# STM32F407VET6_4Layer_Sheet.net
KiCad netlist of a schematic drawn in Altium Designer
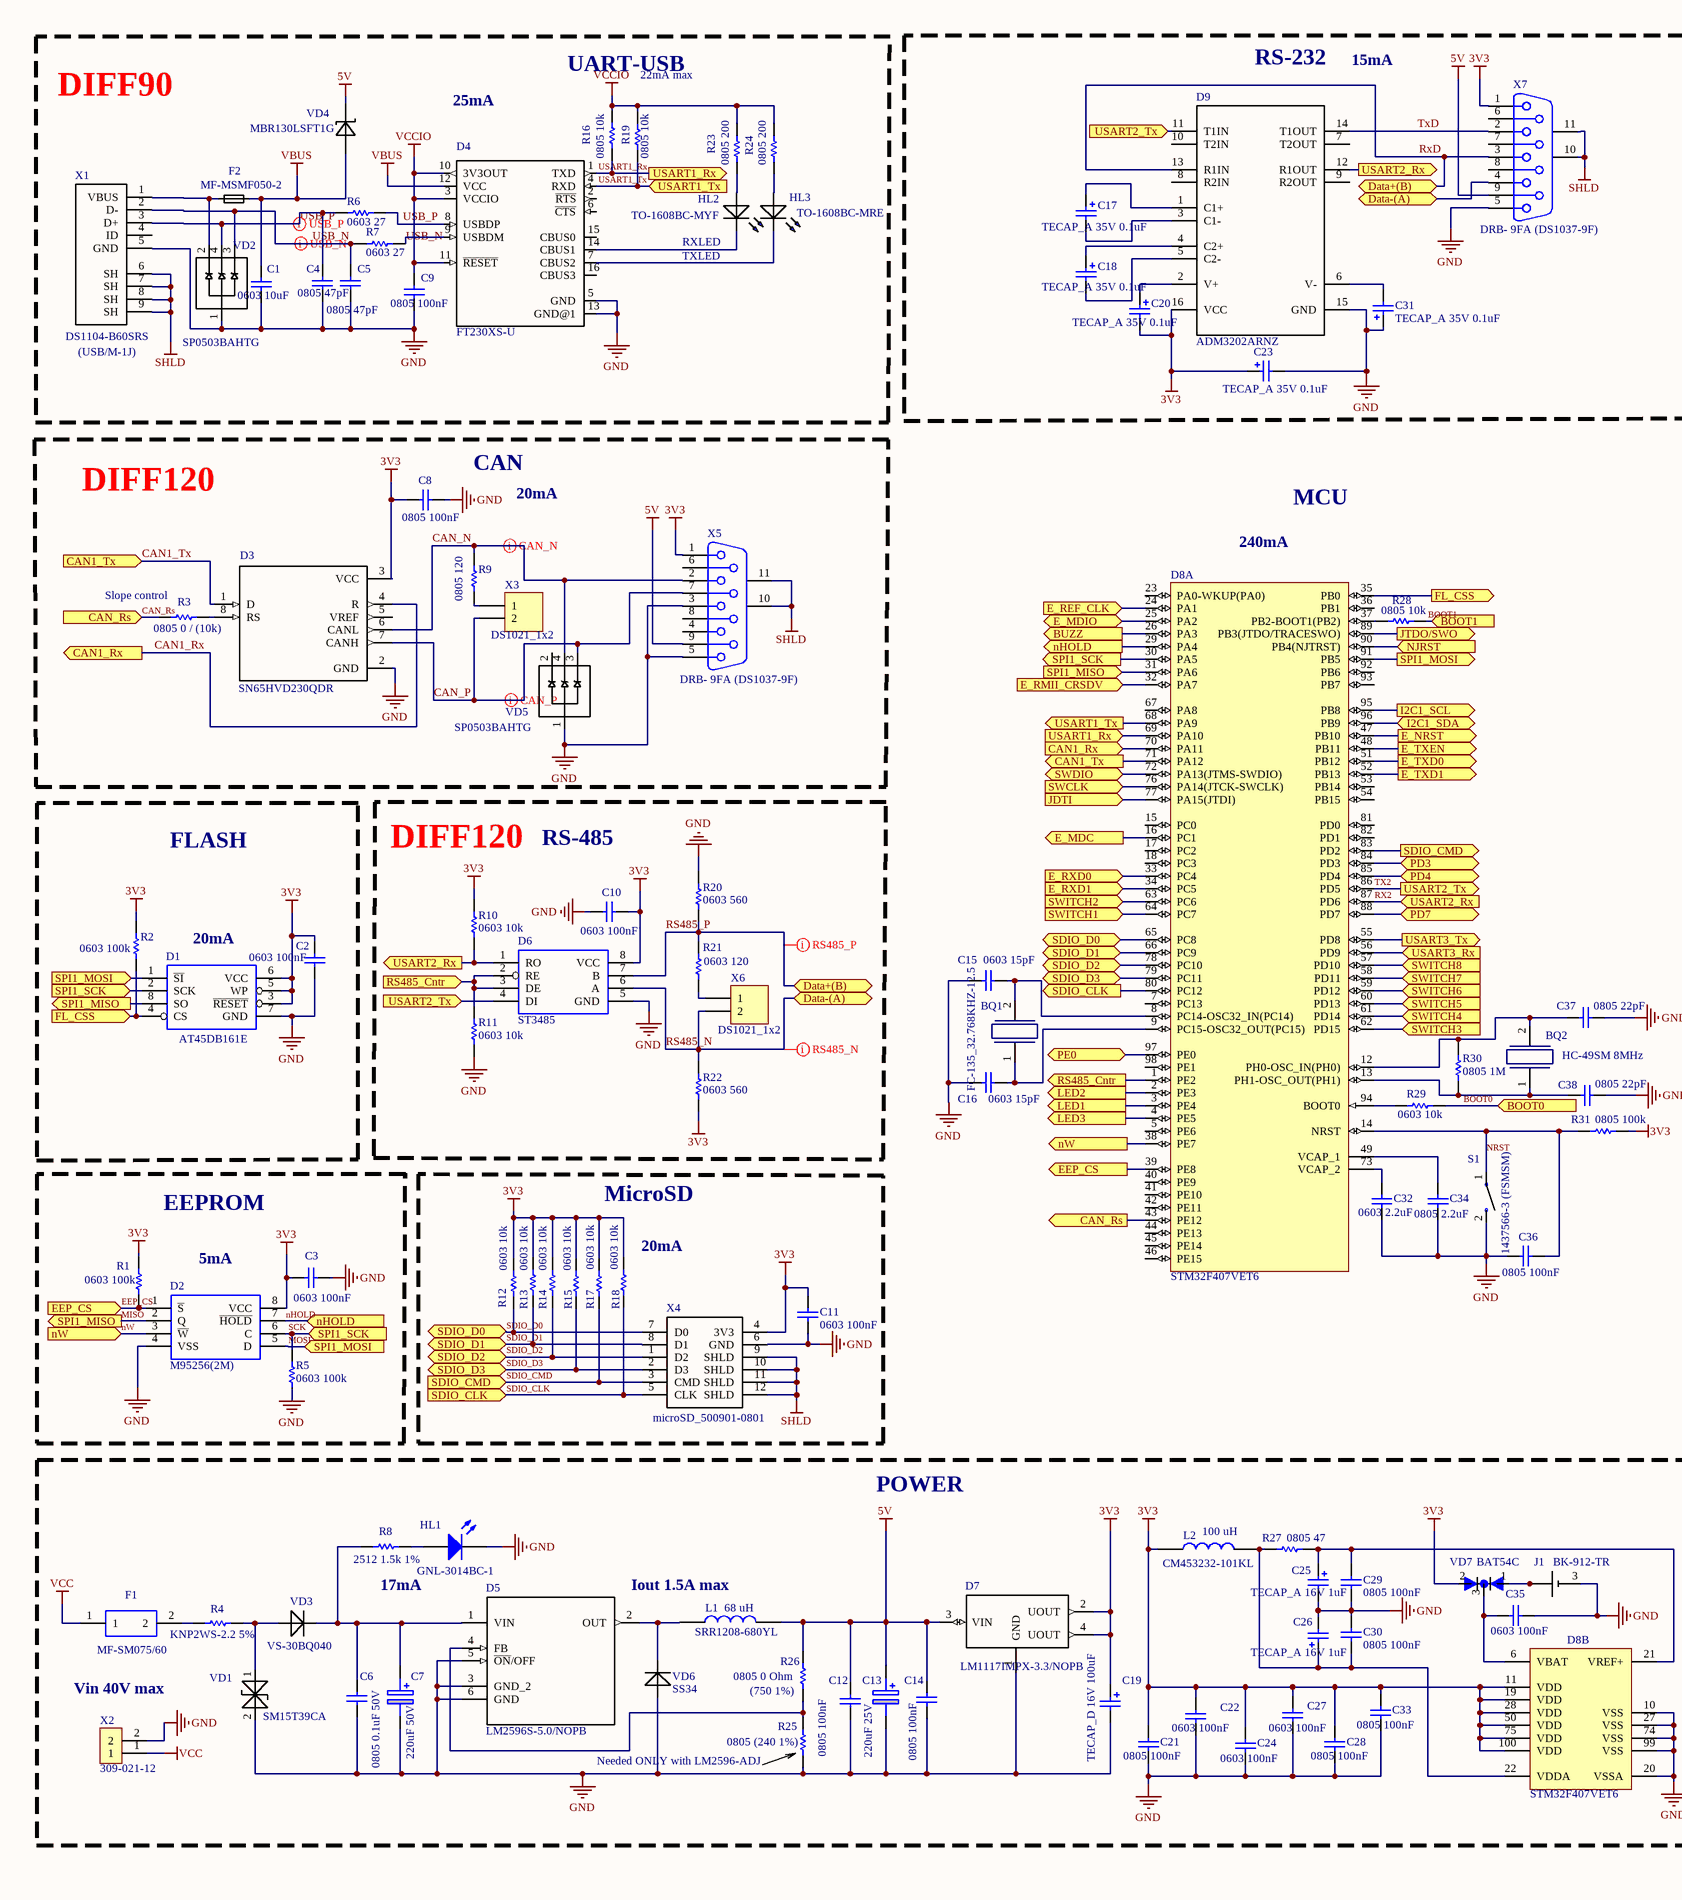
[diagram p0: STM32F407VET6_4Layer_Sheet.SchDoc, left]
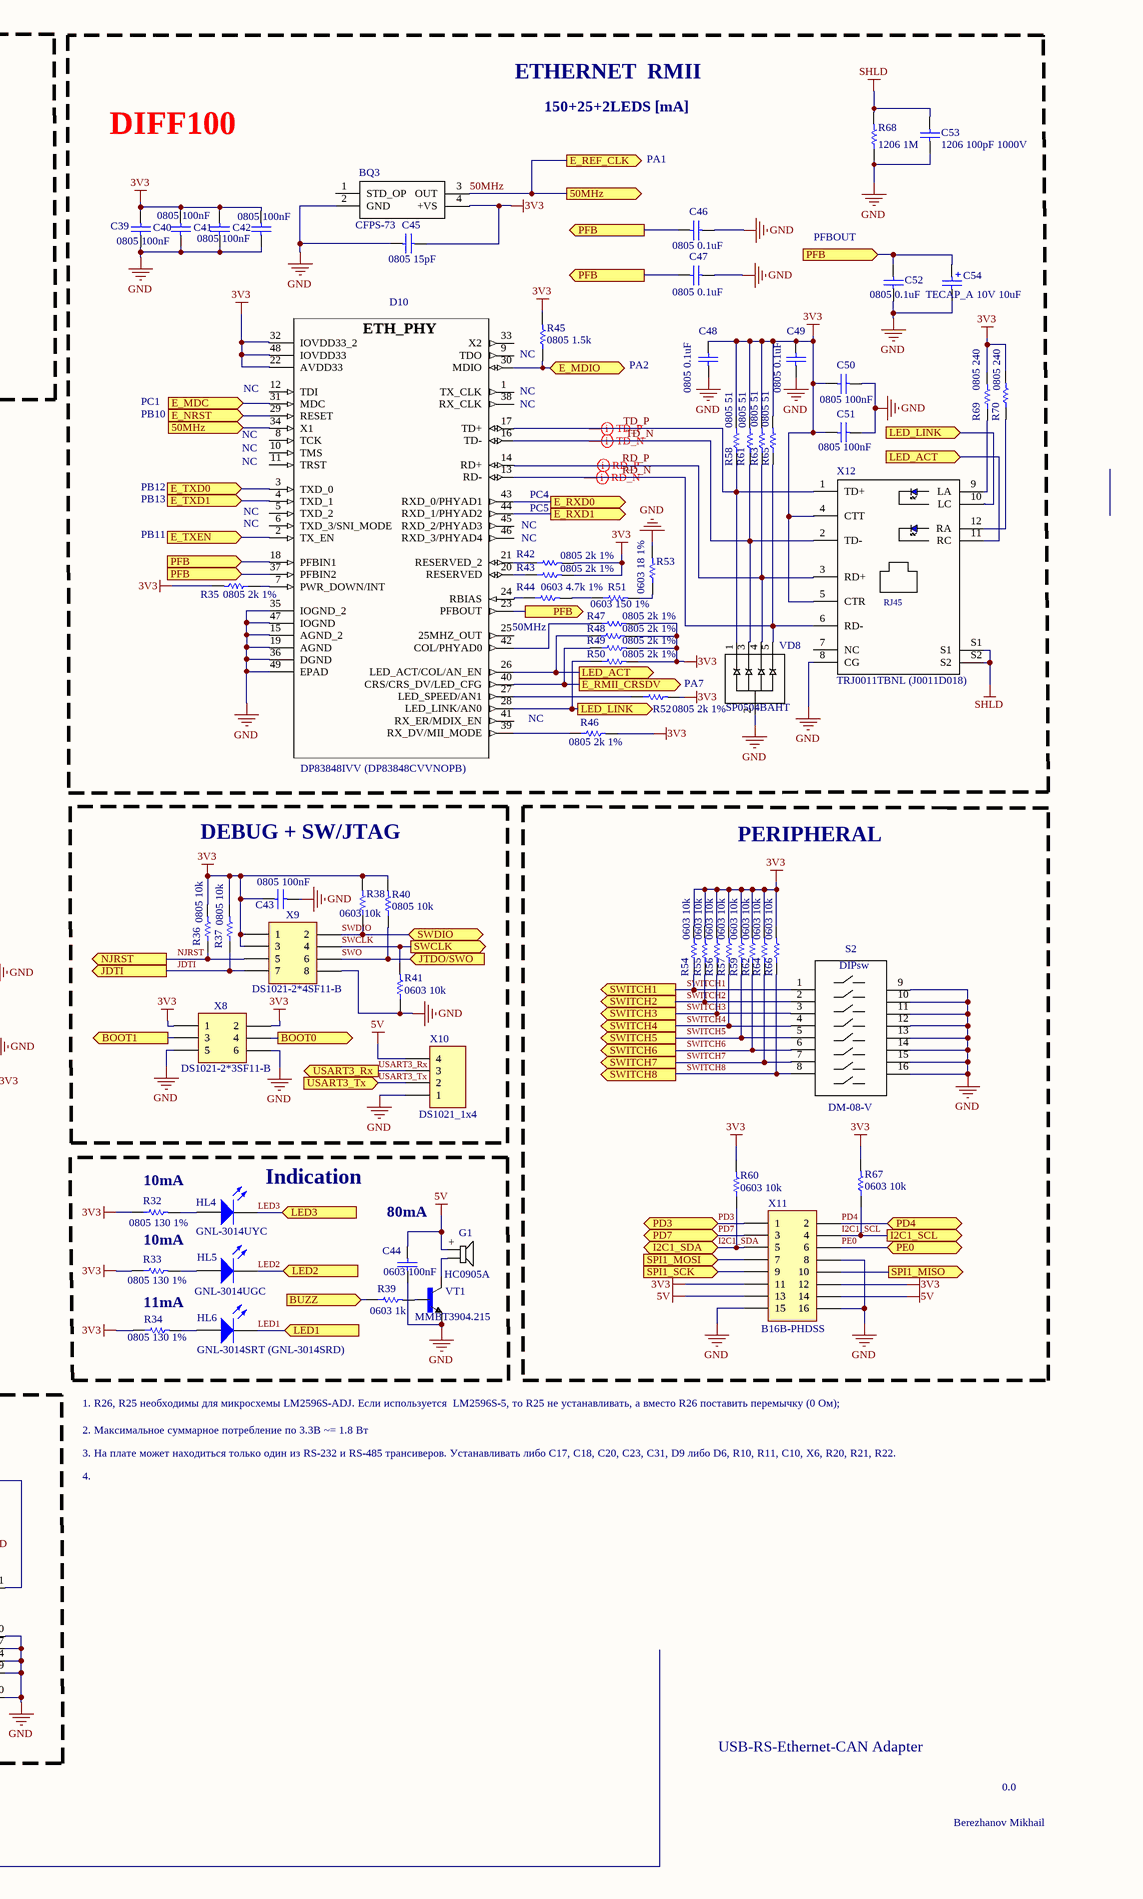
[diagram p1: STM32F407VET6_4Layer_Sheet.SchDoc, right]

(export (version "E")
  (design (tool "Eeschema 10.0.6"))
  (components
    (comp (ref "BQ1")
      (value "FC-135_32.768KHZ-12.5")
      (footprint "FC-135")
      (description "Clock SMD Crystal")
      (libsource (lib "MyCompLib") (part "FC135-32768-7"))
    )
    (comp (ref "BQ2")
      (value "HC-49SM 8MHz")
      (footprint "HC49SM")
      (description "HC49SM")
      (libsource (lib "MyCompLib") (part "HC49SM"))
    )
    (comp (ref "BQ3")
      (value "CFPS-73")
      (footprint "CFPS-73")
      (description "IQD FREQUENCY PRODUCTS - SPXO018044-CFPS-73 - OSCILLATOR FREQUENCY, 50MHZ")
      (libsource (lib "MyCompLib") (part "SPXO018044CFPS-73"))
    )
    (comp (ref "C1")
      (value "0603 10uF")
      (footprint "C_SMD0603")
      (description "SMD Cap 0603")
      (libsource (lib "MyCompLib") (part "C0603"))
    )
    (comp (ref "C2")
      (value "0603 100nF")
      (footprint "C_SMD0603")
      (description "SMD Cap 0603")
      (libsource (lib "MyCompLib") (part "C0603"))
    )
    (comp (ref "C3")
      (value "0603 100nF")
      (footprint "C_SMD0603")
      (description "SMD Cap 0603")
      (libsource (lib "MyCompLib") (part "C0603"))
    )
    (comp (ref "C4")
      (value "0805 47pF")
      (footprint "C_SMD0805")
      (description "SMD Cap 0805")
      (fields (field (name "PUBLISHER") "Altium Limited"))
      (libsource (lib "") (part "C0805_1"))
    )
    (comp (ref "C5")
      (value "0805 47pF")
      (footprint "C_SMD0805")
      (description "SMD Cap 0805")
      (fields (field (name "PUBLISHER") "Altium Limited"))
      (libsource (lib "") (part "C0805_1"))
    )
    (comp (ref "C6")
      (value "0805 0.1uF 50V")
      (footprint "C_SMD0805")
      (description "SMD Cap 0805")
      (fields (field (name "PUBLISHER") "Altium Limited"))
      (libsource (lib "") (part "C0805_1"))
    )
    (comp (ref "C7")
      (value "220uF 50V")
      (footprint "EEEFK1H221P")
      (fields
        (field (name "MANUFACTURER_PART_NUMBER") "EEEFK1H221P")
        (field (name "RS PART NUMBER") "6294598")
      )
      (libsource (lib "MyCompLib") (part "EEEFK1H221P"))
    )
    (comp (ref "C8")
      (value "0805 100nF")
      (footprint "C_SMD0805")
      (description "SMD Cap 0805")
      (fields (field (name "PUBLISHER") "Altium Limited"))
      (libsource (lib "") (part "C0805_1"))
    )
    (comp (ref "C9")
      (value "0805 100nF")
      (footprint "C_SMD0805")
      (description "SMD Cap 0805")
      (fields (field (name "PUBLISHER") "Altium Limited"))
      (libsource (lib "") (part "C0805_1"))
    )
    (comp (ref "C10")
      (value "0603 100nF")
      (footprint "C_SMD0603")
      (description "SMD Cap 0603")
      (libsource (lib "MyCompLib") (part "C0603"))
    )
    (comp (ref "C11")
      (value "0603 100nF")
      (footprint "C_SMD0603")
      (description "SMD Cap 0603")
      (libsource (lib "MyCompLib") (part "C0603"))
    )
    (comp (ref "C12")
      (value "0805 100nF")
      (footprint "C_SMD0805")
      (description "SMD Cap 0805")
      (fields (field (name "PUBLISHER") "Altium Limited"))
      (libsource (lib "") (part "C0805_1"))
    )
    (comp (ref "C13")
      (value "220uF 25V")
      (footprint "EEEFK1H221P")
      (fields
        (field (name "MANUFACTURER_PART_NUMBER") "EEEFK1H221P")
        (field (name "RS PART NUMBER") "6294598")
      )
      (libsource (lib "MyCompLib") (part "EEEFK1H221P"))
    )
    (comp (ref "C14")
      (value "0805 100nF")
      (footprint "C_SMD0805")
      (description "SMD Cap 0805")
      (libsource (lib "MyCompLib") (part "C0805"))
    )
    (comp (ref "C15")
      (value "0603 15pF")
      (footprint "C_SMD0603")
      (description "SMD Cap 0603")
      (libsource (lib "MyCompLib") (part "C0603"))
    )
    (comp (ref "C16")
      (value "0603 15pF")
      (footprint "C_SMD0603")
      (description "SMD Cap 0603")
      (libsource (lib "MyCompLib") (part "C0603"))
    )
    (comp (ref "C17")
      (value "TECAP_A 35V 0.1uF")
      (footprint "TECAP_A")
      (description "Tantalum pol cap type A")
      (libsource (lib "MyCompLib") (part "TECAP_A"))
    )
    (comp (ref "C18")
      (value "TECAP_A 35V 0.1uF")
      (footprint "TECAP_A")
      (description "Tantalum pol cap type A")
      (libsource (lib "MyCompLib") (part "TECAP_A"))
    )
    (comp (ref "C19")
      (value "TECAP_D 16V 100uF")
      (footprint "TECAP_D")
      (description "Tantalum pol cap type D")
      (libsource (lib "MyCompLib") (part "TECAP_D"))
    )
    (comp (ref "C20")
      (value "TECAP_A 35V 0.1uF")
      (footprint "TECAP_A")
      (description "Tantalum pol cap type A")
      (libsource (lib "MyCompLib") (part "TECAP_A"))
    )
    (comp (ref "C21")
      (value "0805 100nF")
      (footprint "C_SMD0805")
      (description "SMD Cap 0805")
      (fields (field (name "PUBLISHER") "Altium Limited"))
      (libsource (lib "") (part "C0805_1"))
    )
    (comp (ref "C22")
      (value "0603 100nF")
      (footprint "C_SMD0603")
      (description "SMD Cap 0603")
      (libsource (lib "MyCompLib") (part "C0603"))
    )
    (comp (ref "C23")
      (value "TECAP_A 35V 0.1uF")
      (footprint "TECAP_A")
      (description "Tantalum pol cap type A")
      (libsource (lib "MyCompLib") (part "TECAP_A"))
    )
    (comp (ref "C24")
      (value "0603 100nF")
      (footprint "C_SMD0603")
      (description "SMD Cap 0603")
      (libsource (lib "MyCompLib") (part "C0603"))
    )
    (comp (ref "C25")
      (value "TECAP_A 16V 1uF")
      (footprint "TECAP_A")
      (description "Tantalum pol cap type A")
      (libsource (lib "MyCompLib") (part "TECAP_A"))
    )
    (comp (ref "C26")
      (value "TECAP_A 16V 1uF")
      (footprint "TECAP_A")
      (description "Tantalum pol cap type A")
      (libsource (lib "MyCompLib") (part "TECAP_A"))
    )
    (comp (ref "C27")
      (value "0603 100nF")
      (footprint "C_SMD0603")
      (description "SMD Cap 0603")
      (libsource (lib "MyCompLib") (part "C0603"))
    )
    (comp (ref "C28")
      (value "0805 100nF")
      (footprint "C_SMD0805")
      (description "SMD Cap 0805")
      (fields (field (name "PUBLISHER") "Altium Limited"))
      (libsource (lib "") (part "C0805_1"))
    )
    (comp (ref "C29")
      (value "0805 100nF")
      (footprint "C_SMD0805")
      (description "SMD Cap 0805")
      (fields (field (name "PUBLISHER") "Altium Limited"))
      (libsource (lib "") (part "C0805_1"))
    )
    (comp (ref "C30")
      (value "0805 100nF")
      (footprint "C_SMD0805")
      (description "SMD Cap 0805")
      (fields (field (name "PUBLISHER") "Altium Limited"))
      (libsource (lib "") (part "C0805_1"))
    )
    (comp (ref "C31")
      (value "TECAP_A 35V 0.1uF")
      (footprint "TECAP_A")
      (description "Tantalum pol cap type A")
      (libsource (lib "MyCompLib") (part "TECAP_A"))
    )
    (comp (ref "C32")
      (value "0603 2.2uF")
      (footprint "C_SMD0603")
      (description "SMD Cap 0603")
      (libsource (lib "MyCompLib") (part "C0603"))
    )
    (comp (ref "C33")
      (value "0805 100nF")
      (footprint "C_SMD0805")
      (description "SMD Cap 0805")
      (fields (field (name "PUBLISHER") "Altium Limited"))
      (libsource (lib "") (part "C0805_1"))
    )
    (comp (ref "C34")
      (value "0805 2.2uF")
      (footprint "C_SMD0805")
      (description "SMD Cap 0805")
      (fields (field (name "PUBLISHER") "Altium Limited"))
      (libsource (lib "") (part "C0805_1"))
    )
    (comp (ref "C35")
      (value "0603 100nF")
      (footprint "C_SMD0603")
      (description "SMD Cap 0603")
      (libsource (lib "MyCompLib") (part "C0603"))
    )
    (comp (ref "C36")
      (value "0805 100nF")
      (footprint "C_SMD0805")
      (description "SMD Cap 0805")
      (fields (field (name "PUBLISHER") "Altium Limited"))
      (libsource (lib "") (part "C0805_1"))
    )
    (comp (ref "C37")
      (value "0805 22pF")
      (footprint "C_SMD0805")
      (description "SMD Cap 0805")
      (fields (field (name "PUBLISHER") "Altium Limited"))
      (libsource (lib "") (part "C0805_1"))
    )
    (comp (ref "C38")
      (value "0805 22pF")
      (footprint "C_SMD0805")
      (description "SMD Cap 0805")
      (fields (field (name "PUBLISHER") "Altium Limited"))
      (libsource (lib "") (part "C0805_1"))
    )
    (comp (ref "C39")
      (value "0805 100nF")
      (footprint "C_SMD0805")
      (description "SMD Cap 0805")
      (fields (field (name "PUBLISHER") "Altium Limited"))
      (libsource (lib "") (part "C0805_1"))
    )
    (comp (ref "C40")
      (value "0805 100nF")
      (footprint "C_SMD0805")
      (description "SMD Cap 0805")
      (fields (field (name "PUBLISHER") "Altium Limited"))
      (libsource (lib "") (part "C0805_1"))
    )
    (comp (ref "C41")
      (value "0805 100nF")
      (footprint "C_SMD0805")
      (description "SMD Cap 0805")
      (fields (field (name "PUBLISHER") "Altium Limited"))
      (libsource (lib "") (part "C0805_1"))
    )
    (comp (ref "C42")
      (value "0805 100nF")
      (footprint "C_SMD0805")
      (description "SMD Cap 0805")
      (fields (field (name "PUBLISHER") "Altium Limited"))
      (libsource (lib "") (part "C0805_1"))
    )
    (comp (ref "C43")
      (value "0805 100nF")
      (footprint "C_SMD0805")
      (description "SMD Cap 0805")
      (fields (field (name "PUBLISHER") "Altium Limited"))
      (libsource (lib "") (part "C0805_1"))
    )
    (comp (ref "C44")
      (value "0603 100nF")
      (footprint "C_SMD0603")
      (description "SMD Cap 0603")
      (libsource (lib "MyCompLib") (part "C0603"))
    )
    (comp (ref "C45")
      (value "0805 15pF")
      (footprint "C_SMD0805")
      (description "SMD Cap 0805")
      (fields (field (name "PUBLISHER") "Altium Limited"))
      (libsource (lib "") (part "C0805_1"))
    )
    (comp (ref "C46")
      (value "0805 0.1uF")
      (footprint "C_SMD0805")
      (description "SMD Cap 0805")
      (fields (field (name "PUBLISHER") "Altium Limited"))
      (libsource (lib "") (part "C0805_1"))
    )
    (comp (ref "C47")
      (value "0805 0.1uF")
      (footprint "C_SMD0805")
      (description "SMD Cap 0805")
      (fields (field (name "PUBLISHER") "Altium Limited"))
      (libsource (lib "") (part "C0805_1"))
    )
    (comp (ref "C48")
      (value "0805 0.1uF")
      (footprint "C_SMD0805")
      (description "SMD Cap 0805")
      (fields (field (name "PUBLISHER") "Altium Limited"))
      (libsource (lib "") (part "C0805_1"))
    )
    (comp (ref "C49")
      (value "0805 0.1uF")
      (footprint "C_SMD0805")
      (description "SMD Cap 0805")
      (fields (field (name "PUBLISHER") "Altium Limited"))
      (libsource (lib "") (part "C0805_1"))
    )
    (comp (ref "C50")
      (value "0805 100nF")
      (footprint "C_SMD0805")
      (description "SMD Cap 0805")
      (fields (field (name "PUBLISHER") "Altium Limited"))
      (libsource (lib "") (part "C0805_1"))
    )
    (comp (ref "C51")
      (value "0805 100nF")
      (footprint "C_SMD0805")
      (description "SMD Cap 0805")
      (fields (field (name "PUBLISHER") "Altium Limited"))
      (libsource (lib "") (part "C0805_1"))
    )
    (comp (ref "C52")
      (value "0805 0.1uF")
      (footprint "C_SMD0805")
      (description "SMD Cap 0805")
      (fields (field (name "PUBLISHER") "Altium Limited"))
      (libsource (lib "") (part "C0805_1"))
    )
    (comp (ref "C53")
      (value "1206 100pF 1000V")
      (footprint "C_SMD1206")
      (description "SMD Cap 1206")
      (fields (field (name "PUBLISHER") "Altium Limited"))
      (libsource (lib "MyCompLib") (part "C1206"))
    )
    (comp (ref "C54")
      (value "TECAP_A 10V 10uF")
      (footprint "TECAP_A")
      (description "Tantalum pol cap type A")
      (libsource (lib "MyCompLib") (part "TECAP_A"))
    )
    (comp (ref "D1")
      (value "AT45DB161E")
      (footprint "SOIC8(5.3mm)")
      (description "SPI FLASH 16Mbit(528 bytes x 4096 pages)")
      (libsource (lib "MyCompLib") (part "AT45DB161E"))
    )
    (comp (ref "D2")
      (value "M95256(2M)")
      (footprint "SOIC8 (SO-8)")
      (description "M95256-WMN6TP, Serial EEPROM Memory 256kbit, Serial-SPI, 60ns 2.5  5.5 V, 8-Pin SOIC")
      (libsource (lib "MyCompLib") (part "M95256(2M)-WMN6TP"))
    )
    (comp (ref "D3")
      (value "SN65HVD230QDR")
      (footprint "SOIC8 (SO-8)")
      (description "3.3-V CAN Transceiver with Standby Mode 8-SOIC -40 to 125")
      (fields (field (name "MF") "Texas Instruments"))
      (libsource (lib "MyCompLib") (part "SN65HVD230QDR"))
    )
    (comp (ref "D4")
      (value "FT230XS-U")
      (footprint "SSOP16")
      (description "FT230XS-U, USB Controller, 3MBd, USB 1.1, USB 2.0, 5 V, 16-Pin SSOP")
      (fields (field (name "MF") "FTDI,"))
      (libsource (lib "MyCompLib") (part "FT230XS-U"))
    )
    (comp (ref "D5")
      (value "LM2596S-5.0/NOPB")
      (footprint "TO263-5")
      (description "SIMPLE SWITCHER&#174; 4.5V to 40V, 3A Low Component Count Step-Down Regulator")
      (libsource (lib "MyCompLib") (part "LM2596S"))
    )
    (comp (ref "D6")
      (value "ST3485")
      (footprint "SOIC8 (SO-8)")
      (description "3.3 V low power transceiver for RS-485")
      (libsource (lib "MyCompLib") (part "ST3485"))
    )
    (comp (ref "D7")
      (value "LM1117IMPX-3.3/NOPB")
      (footprint "SOT223")
      (description "Линейный регулятор с низким падением напряжения, 3.3В")
      (libsource (lib "MyCompLib") (part "LM1117-3.3"))
    )
    (comp (ref "D8")
      (value "STM32F407VET6")
      (footprint "STM-LQFP100_N")
      (fields (field (name "MANUFACTURER") "STMicroelectronics"))
      (libsource (lib "STMicroelectronics STM32 F4") (part "STM32F407VET6"))
    )
    (comp (ref "D9")
      (value "ADM3202ARNZ")
      (footprint "SOIC-16")
      (description "3.3V SMD RS232-UART")
      (libsource (lib "MyCompLib") (part "ADM3202ARNZ"))
    )
    (comp (ref "D10")
      (value "DP83848IVV (DP83848CVVNOPB)")
      (footprint "QFP48")
      (description "ETH Transciever")
      (libsource (lib "MyCompLib") (part "DP83848CVVNOPB"))
    )
    (comp (ref "F1")
      (value "MF-SM075/60")
      (footprint "MF-SM075/60")
      (libsource (lib "MyCompLib") (part "MF-SM075/60"))
    )
    (comp (ref "F2")
      (value "MF-MSMF050-2")
      (footprint "FUSE1812x0")
      (description "PTC Resettable Fuse 0.5A_hold_ 1A_trip_ 15V 100A 0.8W 0.15s 0.15Ohm SMD Solder Pad 1812 T/R")
      (libsource (lib "MyCompLib") (part "MF-MSMF050-2"))
    )
    (comp (ref "G1")
      (value "HC0905A")
      (footprint "HC090xA")
      (description "Buzzer 5V 80mA h=5mm d=9.5mm 3200Hz")
      (libsource (lib "MyCompLib") (part "HC0905A"))
    )
    (comp (ref "HL1")
      (value "GNL-3014BC-1")
      (footprint "LED3mm")
      (libsource (lib "MyCompLib") (part "LED_0_25_4"))
    )
    (comp (ref "HL2")
      (value "TO-1608BC-MYF")
      (footprint "LED_SMD1608GREEN")
      (description "TO-1608BC-BF \\  TO-1608BC-MRE")
      (libsource (lib "MyCompLib") (part "LED_SMD"))
    )
    (comp (ref "HL3")
      (value "TO-1608BC-MRE")
      (footprint "LED_SMD1608")
      (description "TO-1608BC-BF \\  TO-1608BC-MRE")
      (libsource (lib "MyCompLib") (part "LED_SMD"))
    )
    (comp (ref "HL4")
      (value "GNL-3014UYC")
      (footprint "LED3mm")
      (description "Светодиод желтый 25° d=3мм 1000мКд 589нМ (Yellow)")
      (libsource (lib "MyCompLib") (part "LED_0_25_4"))
    )
    (comp (ref "HL5")
      (value "GNL-3014UGC")
      (footprint "LED3mm")
      (description "Светодиод зеленый 25° d=3мм 1200мКд 572нМ (Green)")
      (libsource (lib "MyCompLib") (part "LED_0_25_4"))
    )
    (comp (ref "HL6")
      (value "GNL-3014SRT (GNL-3014SRD)")
      (footprint "LED3mm")
      (description "Светодиод красный 20° d=3мм 200мКд 660нМ (Red)")
      (libsource (lib "MyCompLib") (part "LED_0_25_4"))
    )
    (comp (ref "J1")
      (value "BK-912-TR")
      (footprint "BK-912-TR")
      (description "Holder Coin Cell 20mm Smd")
      (libsource (lib "MyCompLib") (part "BK-912-TR"))
    )
    (comp (ref "L1")
      (value "SRR1208-680YL")
      (footprint "SRR1208")
      (description "Fixed Inductors 330uH 10% SMD 1208")
      (fields (field (name "MANUFACTURER_PART_NUMBER") "SRR1208-682KL"))
      (libsource (lib "MyCompLib") (part "SRR1208-682KL"))
    )
    (comp (ref "L2")
      (value "CM453232-101KL")
      (footprint "INDPM4532")
      (description "BOURNS - CM453232-101KL - INDUCTOR, 4532 CASE, 100UH")
      (fields
        (field (name "MANUFACTURER_PART_NUMBER") "CM453232-471KL")
        (field (name "RS PART NUMBER") "6934353")
      )
      (libsource (lib "MyCompLib") (part "CM453232-471KL"))
    )
    (comp (ref "R1")
      (value "0603 100k")
      (footprint "R_SMD0603")
      (description "SMD Res 0603")
      (libsource (lib "MyCompLib") (part "R0603"))
    )
    (comp (ref "R2")
      (value "0603 100k")
      (footprint "R_SMD0603")
      (description "SMD Res 0603")
      (libsource (lib "MyCompLib") (part "R0603"))
    )
    (comp (ref "R3")
      (value "0805 0 / (10k)")
      (footprint "R_SMD0805")
      (description "SMD Res 0805")
      (libsource (lib "MyCompLib") (part "R0805"))
    )
    (comp (ref "R4")
      (value "KNP2WS-2.2 5%")
      (footprint "KNP2WS")
      (description "Резисторы с проволочной обмоткой – сквозное отверстие 2.2ohm 2W 5%")
      (libsource (lib "MyCompLib") (part "KNP2WS"))
    )
    (comp (ref "R5")
      (value "0603 100k")
      (footprint "R_SMD0603")
      (description "SMD Res 0603")
      (libsource (lib "MyCompLib") (part "R0603"))
    )
    (comp (ref "R6")
      (value "0603 27")
      (footprint "R_SMD0603")
      (description "SMD Res 0603")
      (libsource (lib "MyCompLib") (part "R0603"))
    )
    (comp (ref "R7")
      (value "0603 27")
      (footprint "R_SMD0603")
      (description "SMD Res 0603")
      (libsource (lib "MyCompLib") (part "R0603"))
    )
    (comp (ref "R8")
      (value "2512 1.5k 1%")
      (footprint "R_SMD2512")
      (description "SMD Res 2512")
      (libsource (lib "MyCompLib") (part "R2512"))
    )
    (comp (ref "R9")
      (value "0805 120")
      (footprint "R_SMD0805")
      (description "SMD Res 0805")
      (libsource (lib "MyCompLib") (part "R0805"))
    )
    (comp (ref "R10")
      (value "0603 10k")
      (footprint "R_SMD0603")
      (description "SMD Res 0603")
      (libsource (lib "MyCompLib") (part "R0603"))
    )
    (comp (ref "R11")
      (value "0603 10k")
      (footprint "R_SMD0603")
      (description "SMD Res 0603")
      (libsource (lib "MyCompLib") (part "R0603"))
    )
    (comp (ref "R12")
      (value "0603 10k")
      (footprint "R_SMD0603")
      (description "SMD Res 0603")
      (libsource (lib "MyCompLib") (part "R0603"))
    )
    (comp (ref "R13")
      (value "0603 10k")
      (footprint "R_SMD0603")
      (description "SMD Res 0603")
      (libsource (lib "MyCompLib") (part "R0603"))
    )
    (comp (ref "R14")
      (value "0603 10k")
      (footprint "R_SMD0603")
      (description "SMD Res 0603")
      (libsource (lib "MyCompLib") (part "R0603"))
    )
    (comp (ref "R15")
      (value "0603 10k")
      (footprint "R_SMD0603")
      (description "SMD Res 0603")
      (libsource (lib "MyCompLib") (part "R0603"))
    )
    (comp (ref "R16")
      (value "0805 10k")
      (footprint "R_SMD0805")
      (description "SMD Res 0805")
      (libsource (lib "MyCompLib") (part "R0805"))
    )
    (comp (ref "R17")
      (value "0603 10k")
      (footprint "R_SMD0603")
      (description "SMD Res 0603")
      (libsource (lib "MyCompLib") (part "R0603"))
    )
    (comp (ref "R18")
      (value "0603 10k")
      (footprint "R_SMD0603")
      (description "SMD Res 0603")
      (libsource (lib "MyCompLib") (part "R0603"))
    )
    (comp (ref "R19")
      (value "0805 10k")
      (footprint "R_SMD0805")
      (description "SMD Res 0805")
      (libsource (lib "MyCompLib") (part "R0805"))
    )
    (comp (ref "R20")
      (value "0603 560")
      (footprint "R_SMD0603")
      (description "SMD Res 0603")
      (libsource (lib "MyCompLib") (part "R0603"))
    )
    (comp (ref "R21")
      (value "0603 120")
      (footprint "R_SMD0603")
      (description "SMD Res 0603")
      (libsource (lib "MyCompLib") (part "R0603"))
    )
    (comp (ref "R22")
      (value "0603 560")
      (footprint "R_SMD0603")
      (description "SMD Res 0603")
      (libsource (lib "MyCompLib") (part "R0603"))
    )
    (comp (ref "R23")
      (value "0805 200")
      (footprint "R_SMD0805")
      (description "SMD Res 0805")
      (libsource (lib "MyCompLib") (part "R0805"))
    )
    (comp (ref "R24")
      (value "0805 200")
      (footprint "R_SMD0805")
      (description "SMD Res 0805")
      (libsource (lib "MyCompLib") (part "R0805"))
    )
    (comp (ref "R25")
      (value "0805 (240 1%)")
      (footprint "R_SMD0805")
      (description "SMD Res 0805")
      (libsource (lib "MyCompLib") (part "R0805"))
    )
    (comp (ref "R26")
      (value "0805 0 Ohm")
      (footprint "C_SMD0805")
      (description "SMD Res 0805")
      (libsource (lib "MyCompLib") (part "R0805"))
    )
    (comp (ref "R27")
      (value "0805 47")
      (footprint "R_SMD0805")
      (description "SMD Res 0805")
      (libsource (lib "MyCompLib") (part "R0805"))
    )
    (comp (ref "R28")
      (value "0805 10k")
      (footprint "R_SMD0805")
      (description "SMD Res 0805")
      (libsource (lib "MyCompLib") (part "R0805"))
    )
    (comp (ref "R29")
      (value "0603 10k")
      (footprint "R_SMD0603")
      (description "SMD Res 0603")
      (libsource (lib "MyCompLib") (part "R0603"))
    )
    (comp (ref "R30")
      (value "0805 1M")
      (footprint "R_SMD0805")
      (description "SMD Res 0805")
      (libsource (lib "MyCompLib") (part "R0805"))
    )
    (comp (ref "R31")
      (value "0805 100k")
      (footprint "C_SMD0805")
      (description "SMD Res 0805")
      (libsource (lib "MyCompLib") (part "R0805"))
    )
    (comp (ref "R32")
      (value "0805 130 1%")
      (footprint "R_SMD0805")
      (description "SMD Res 0805")
      (libsource (lib "MyCompLib") (part "R0805"))
    )
    (comp (ref "R33")
      (value "0805 130 1%")
      (footprint "R_SMD0805")
      (description "SMD Res 0805")
      (libsource (lib "MyCompLib") (part "R0805"))
    )
    (comp (ref "R34")
      (value "0805 130 1%")
      (footprint "R_SMD0805")
      (description "SMD Res 0805")
      (libsource (lib "MyCompLib") (part "R0805"))
    )
    (comp (ref "R35")
      (value "0805 2k 1%")
      (footprint "R_SMD0805")
      (description "SMD Res 0805")
      (libsource (lib "MyCompLib") (part "R0805"))
    )
    (comp (ref "R36")
      (value "0805 10k")
      (footprint "R_SMD0805")
      (description "SMD Res 0805")
      (libsource (lib "MyCompLib") (part "R0805"))
    )
    (comp (ref "R37")
      (value "0805 10k")
      (footprint "R_SMD0805")
      (description "SMD Res 0805")
      (libsource (lib "MyCompLib") (part "R0805"))
    )
    (comp (ref "R38")
      (value "0603 10k")
      (footprint "R_SMD0603")
      (description "SMD Res 0603")
      (libsource (lib "MyCompLib") (part "R0603"))
    )
    (comp (ref "R39")
      (value "0603 1k")
      (footprint "R_SMD0603")
      (description "SMD Res 0603")
      (libsource (lib "MyCompLib") (part "R0603"))
    )
    (comp (ref "R40")
      (value "0805 10k")
      (footprint "R_SMD0805")
      (description "SMD Res 0805")
      (libsource (lib "MyCompLib") (part "R0805"))
    )
    (comp (ref "R41")
      (value "0603 10k")
      (footprint "R_SMD0603")
      (description "SMD Res 0603")
      (libsource (lib "MyCompLib") (part "R0603"))
    )
    (comp (ref "R42")
      (value "0805 2k 1%")
      (footprint "R_SMD0805")
      (description "SMD Res 0805")
      (libsource (lib "MyCompLib") (part "R0805"))
    )
    (comp (ref "R43")
      (value "0805 2k 1%")
      (footprint "R_SMD0805")
      (description "SMD Res 0805")
      (libsource (lib "MyCompLib") (part "R0805"))
    )
    (comp (ref "R44")
      (value "0603 4.7k 1%")
      (footprint "R_SMD0603")
      (description "SMD Res 0603")
      (libsource (lib "MyCompLib") (part "R0603"))
    )
    (comp (ref "R45")
      (value "0805 1.5k")
      (footprint "R_SMD0805")
      (description "SMD Res 0805")
      (libsource (lib "MyCompLib") (part "R0805"))
    )
    (comp (ref "R46")
      (value "0805 2k 1%")
      (footprint "R_SMD0805")
      (description "SMD Res 0805")
      (libsource (lib "MyCompLib") (part "R0805"))
    )
    (comp (ref "R47")
      (value "0805 2k 1%")
      (footprint "R_SMD0805")
      (description "SMD Res 0805")
      (libsource (lib "MyCompLib") (part "R0805"))
    )
    (comp (ref "R48")
      (value "0805 2k 1%")
      (footprint "R_SMD0805")
      (description "SMD Res 0805")
      (libsource (lib "MyCompLib") (part "R0805"))
    )
    (comp (ref "R49")
      (value "0805 2k 1%")
      (footprint "R_SMD0805")
      (description "SMD Res 0805")
      (libsource (lib "MyCompLib") (part "R0805"))
    )
    (comp (ref "R50")
      (value "0805 2k 1%")
      (footprint "R_SMD0805")
      (description "SMD Res 0805")
      (libsource (lib "MyCompLib") (part "R0805"))
    )
    (comp (ref "R51")
      (value "0603 150 1%")
      (footprint "R_SMD0603")
      (description "SMD Res 0603")
      (libsource (lib "MyCompLib") (part "R0603"))
    )
    (comp (ref "R52")
      (value "0805 2k 1%")
      (footprint "R_SMD0805")
      (description "SMD Res 0805")
      (libsource (lib "MyCompLib") (part "R0805"))
    )
    (comp (ref "R53")
      (value "0603 18 1%")
      (footprint "R_SMD0603")
      (description "SMD Res 0603")
      (libsource (lib "MyCompLib") (part "R0603"))
    )
    (comp (ref "R54")
      (value "0603 10k")
      (footprint "R_SMD0603")
      (description "SMD Res 0603")
      (libsource (lib "MyCompLib") (part "R0603"))
    )
    (comp (ref "R55")
      (value "0603 10k")
      (footprint "R_SMD0603")
      (description "SMD Res 0603")
      (libsource (lib "MyCompLib") (part "R0603"))
    )
    (comp (ref "R56")
      (value "0603 10k")
      (footprint "R_SMD0603")
      (description "SMD Res 0603")
      (libsource (lib "MyCompLib") (part "R0603"))
    )
    (comp (ref "R57")
      (value "0603 10k")
      (footprint "R_SMD0603")
      (description "SMD Res 0603")
      (libsource (lib "MyCompLib") (part "R0603"))
    )
    (comp (ref "R58")
      (value "0805 51")
      (footprint "R_SMD0805")
      (description "SMD Res 0805")
      (libsource (lib "MyCompLib") (part "R0805"))
    )
    (comp (ref "R59")
      (value "0603 10k")
      (footprint "R_SMD0603")
      (description "SMD Res 0603")
      (libsource (lib "MyCompLib") (part "R0603"))
    )
    (comp (ref "R60")
      (value "0603 10k")
      (footprint "R_SMD0603")
      (description "SMD Res 0603")
      (libsource (lib "MyCompLib") (part "R0603"))
    )
    (comp (ref "R61")
      (value "0805 51")
      (footprint "R_SMD0805")
      (description "SMD Res 0805")
      (libsource (lib "MyCompLib") (part "R0805"))
    )
    (comp (ref "R62")
      (value "0603 10k")
      (footprint "R_SMD0603")
      (description "SMD Res 0603")
      (libsource (lib "MyCompLib") (part "R0603"))
    )
    (comp (ref "R63")
      (value "0805 51")
      (footprint "R_SMD0805")
      (description "SMD Res 0805")
      (libsource (lib "MyCompLib") (part "R0805"))
    )
    (comp (ref "R64")
      (value "0603 10k")
      (footprint "R_SMD0603")
      (description "SMD Res 0603")
      (libsource (lib "MyCompLib") (part "R0603"))
    )
    (comp (ref "R65")
      (value "0805 51")
      (footprint "R_SMD0805")
      (description "SMD Res 0805")
      (libsource (lib "MyCompLib") (part "R0805"))
    )
    (comp (ref "R66")
      (value "0603 10k")
      (footprint "R_SMD0603")
      (description "SMD Res 0603")
      (libsource (lib "MyCompLib") (part "R0603"))
    )
    (comp (ref "R67")
      (value "0603 10k")
      (footprint "R_SMD0603")
      (description "SMD Res 0603")
      (libsource (lib "MyCompLib") (part "R0603"))
    )
    (comp (ref "R68")
      (value "1206 1M")
      (footprint "R_SMD1206")
      (description "SMD Res 1206")
      (libsource (lib "MyCompLib") (part "R1206"))
    )
    (comp (ref "R69")
      (value "0805 240")
      (footprint "R_SMD0805")
      (description "SMD Res 0805")
      (libsource (lib "MyCompLib") (part "R0805"))
    )
    (comp (ref "R70")
      (value "0805 240")
      (footprint "R_SMD0805")
      (description "SMD Res 0805")
      (libsource (lib "MyCompLib") (part "R0805"))
    )
    (comp (ref "S1")
      (value "1437566-3 (FSMSM)")
      (footprint "1437566-3")
      (description "FSMSM=3.5X6 SMT TACT")
      (fields (field (name "MP") "1437566-3") (field (name "MF") "TE Connectivity"))
      (libsource (lib "MyCompLib") (part "1437566-3"))
    )
    (comp (ref "S2")
      (value "DM-08-V")
      (footprint "DM-08-V")
      (description "SMD DIPSWITCH8")
      (libsource (lib "MyCompLib") (part "DM-08-V"))
    )
    (comp (ref "VD1")
      (value "SM15T39CA")
      (footprint "DO214AB SMC")
      (description "TVS Diode Bi-Directional SM15T39CA 69.7V, 1500W, SMC 2-Pin")
      (libsource (lib "MyCompLib") (part "SM15T39CA"))
    )
    (comp (ref "VD2")
      (value "SP0503BAHTG")
      (footprint "SP0503BAHTG")
      (description "SP050xBA Series 8 V 30 pF Uni-Directional SMT TVS Avalanche Diode Array SOT-143")
      (fields (field (name "MF") "Littelfuse Inc."))
      (libsource (lib "MyCompLib") (part "SP0503BAHTG"))
    )
    (comp (ref "VD3")
      (value "VS-30BQ040")
      (footprint "DO214AB SMC")
      (description "VS-30BQ040-M3/9AT Vishay VS-30BQ040-M3/9AT, SMT Schottky Diode, 40V 4A, 2-Pin DO-214AB")
      (libsource (lib "MyCompLib") (part "VS-30BQ040"))
    )
    (comp (ref "VD4")
      (value "MBR130LSFT1G")
      (footprint "SOD-123FL")
      (description "Schottky Barrier Diodes, 1A to 2A, ON Semiconductor")
      (libsource (lib "MyCompLib") (part "MBR130LSFT1G"))
    )
    (comp (ref "VD5")
      (value "SP0503BAHTG")
      (footprint "SP0503BAHTG")
      (description "SP050xBA Series 8 V 30 pF Uni-Directional SMT TVS Avalanche Diode Array SOT-143")
      (fields (field (name "MF") "Littelfuse Inc."))
      (libsource (lib "MyCompLib") (part "SP0503BAHTG"))
    )
    (comp (ref "VD6")
      (value "SS34")
      (footprint "DO214AB SMC")
      (description "Rectifier, Schottky; DO-214AB; 3.0A IF; 0.75V; 40V; 100A IFRM; 10000V/us; 1000pF")
      (libsource (lib "MyCompLib") (part "SS34"))
    )
    (comp (ref "VD7")
      (value "BAT54C")
      (footprint "BAT54C_SOT23-3")
      (description "Small Signal Schottky Diode, Dual Common Cathode, 30 V, 200 mA, 400 mV, 600 mA, 125 C")
      (libsource (lib "MyCompLib") (part "BAT54C"))
    )
    (comp (ref "VD8")
      (value "SP0504BAHT")
      (footprint "SOT23-5")
      (description "TVS Diode-4")
      (libsource (lib "MyCompLib") (part "SP0504BAHT"))
    )
    (comp (ref "VT1")
      (value "MMBT3904.215")
      (footprint "SOT23")
      (description "Транзистор NPN 40В 0.2А [SOT-23-3]")
      (libsource (lib "MyCompLib") (part "MMBT3904.215"))
    )
    (comp (ref "X1")
      (value "DS1104-B60SRS")
      (footprint "MUSB-05-S-B-SM")
      (description "Conn Mini USB 2.0 Type B RCP 5 POS 0.8mm Solder RA SMD 5 Terminal 1 Port Tray")
      (libsource (lib "MyCompLib") (part "MSUB-05 (DS1104)"))
    )
    (comp (ref "X2")
      (value "309-021-12")
      (footprint "390-021-12")
      (description "DG390-5.0-02P (XY118-2P-05) Зажимной Клеммник 2-контактный, 5.0мм угловой")
      (libsource (lib "MyCompLib") (part "309-021-12"))
    )
    (comp (ref "X3")
      (value "DS1021_1x2")
      (footprint "PLD2")
      (description "Вилка штыревая 2.54мм 1x2 прямая тип1")
      (libsource (lib "MyCompLib") (part "DS1021_1x2"))
    )
    (comp (ref "X4")
      (value "microSD_500901-0801")
      (footprint "5009001-0801")
      (description "TransFlash Memory Card,1.1mm hinge type TransFlash Memory Card,1.1mm hinge type")
      (libsource (lib "MyCompLib") (part "microSD_500901-0801"))
    )
    (comp (ref "X5")
      (value "DRB- 9FA (DS1037-9F)")
      (footprint "DRB- 9FA")
      (libsource (lib "MyCompLib") (part "DRB- 9FA (DS1037-9F)"))
    )
    (comp (ref "X6")
      (value "DS1021_1x2")
      (footprint "PLD2")
      (description "Вилка штыревая 2.54мм 1x2 прямая тип1")
      (libsource (lib "MyCompLib") (part "DS1021_1x2"))
    )
    (comp (ref "X7")
      (value "DRB- 9FA (DS1037-9F)")
      (footprint "DRB- 9FA")
      (libsource (lib "MyCompLib") (part "DRB- 9FA (DS1037-9F)"))
    )
    (comp (ref "X8")
      (value "DS1021-2*3SF11-B")
      (footprint "PLD2-3")
      (description "Вилка штыревая 2.54мм 2x3 прямая тип1")
      (libsource (lib "MyCompLib") (part "DS1021_2x3"))
    )
    (comp (ref "X9")
      (value "DS1021-2*4SF11-B")
      (footprint "PLD2-4")
      (description "Вилка штыревая 2.54мм 2x4 прямая тип1")
      (libsource (lib "MyCompLib") (part "DS1021_2x4"))
    )
    (comp (ref "X10")
      (value "DS1021_1x4")
      (footprint "PLD1X4")
      (description "Вилка штыревая 2.54мм 1x4 прямая тип1")
      (libsource (lib "MyCompLib") (part "DS1021_1x4"))
    )
    (comp (ref "X11")
      (value "B16B-PHDSS")
      (footprint "PHD16")
      (description "HEADER, PHD, TOP, 16WAY, 2MM; Pitch Spacing:2mm; No. of Contacts:16Contacts;")
      (libsource (lib "MyCompLib") (part "B16B-PHDSS"))
    )
    (comp (ref "X12")
      (value "TRJ0011TBNL (J0011D018)")
      (footprint "J0011D018")
      (description "Conn RJ-45 F 8 POS 2.54mm Solder RA Thru-Hole 12 Terminal 1 Port Cat 5/Cat 6")
      (libsource (lib "MyCompLib") (part "RJ45 J0011D018"))
    )
  )
  (nets
    (net (code "1") (name "/50MHz") (class "Default")
      (node (ref "BQ3") (pin "3") (pinfunction "OUT_3") (pintype "passive"))
      (node (ref "D10") (pin "34") (pinfunction "X1_34") (pintype "input"))
      (node (ref "D8") (pin "24") (pinfunction "PA1_24") (pintype "bidirectional"))
    )
    (net (code "2") (name "/BOOT0") (class "Default")
      (node (ref "R29") (pin "2") (pinfunction "2_2") (pintype "passive"))
      (node (ref "X8") (pin "4") (pinfunction "4_4") (pintype "passive"))
    )
    (net (code "3") (name "/BOOT1") (class "Default")
      (node (ref "R28") (pin "2") (pinfunction "2_2") (pintype "passive"))
      (node (ref "X8") (pin "3") (pinfunction "3_3") (pintype "passive"))
    )
    (net (code "4") (name "/BUZZ") (class "Default")
      (node (ref "D8") (pin "26") (pinfunction "PA3_26") (pintype "bidirectional"))
      (node (ref "R39") (pin "1") (pinfunction "1_1") (pintype "passive"))
    )
    (net (code "5") (name "/CAN1_Rx") (class "Default")
      (node (ref "D3") (pin "4") (pinfunction "R_4") (pintype "output"))
      (node (ref "D8") (pin "70") (pinfunction "PA11_70") (pintype "bidirectional"))
    )
    (net (code "6") (name "/CAN1_Tx") (class "Default")
      (node (ref "D3") (pin "1") (pinfunction "D_1") (pintype "input"))
      (node (ref "D8") (pin "71") (pinfunction "PA12_71") (pintype "bidirectional"))
    )
    (net (code "7") (name "/CAN_N") (class "Default")
      (node (ref "D3") (pin "6") (pinfunction "CANL_6") (pintype "output"))
      (node (ref "R9") (pin "1") (pinfunction "1_1") (pintype "passive"))
      (node (ref "VD5") (pin "4") (pinfunction "C_4") (pintype "passive"))
      (node (ref "X5") (pin "2") (pinfunction "2_2") (pintype "passive"))
    )
    (net (code "8") (name "/CAN_P") (class "Default")
      (node (ref "D3") (pin "7") (pinfunction "CANH_7") (pintype "output"))
      (node (ref "VD5") (pin "3") (pinfunction "B_3") (pintype "passive"))
      (node (ref "X3") (pin "2") (pinfunction "2_2") (pintype "passive"))
      (node (ref "X5") (pin "7") (pinfunction "7_7") (pintype "passive"))
    )
    (net (code "9") (name "/CAN_Rs") (class "Default")
      (node (ref "D8") (pin "43") (pinfunction "PE12_43") (pintype "bidirectional"))
      (node (ref "R3") (pin "2") (pinfunction "2_2") (pintype "passive"))
    )
    (net (code "10") (name "/EEP_CS") (class "Default")
      (node (ref "D2") (pin "1") (pinfunction "S_1") (pintype "passive"))
      (node (ref "D8") (pin "39") (pinfunction "PE8_39") (pintype "bidirectional"))
      (node (ref "R1") (pin "1") (pinfunction "1_1") (pintype "passive"))
    )
    (net (code "11") (name "/E_MDC") (class "Default")
      (node (ref "D10") (pin "31") (pinfunction "MDC_31") (pintype "input"))
      (node (ref "D8") (pin "16") (pinfunction "PC1_16") (pintype "bidirectional"))
    )
    (net (code "12") (name "/E_MDIO") (class "Default")
      (node (ref "D10") (pin "30") (pinfunction "MDIO_30") (pintype "bidirectional"))
      (node (ref "D8") (pin "25") (pinfunction "PA2_25") (pintype "bidirectional"))
      (node (ref "R45") (pin "1") (pinfunction "1_1") (pintype "passive"))
    )
    (net (code "13") (name "/E_NRST") (class "Default")
      (node (ref "D10") (pin "29") (pinfunction "RESET_29") (pintype "input"))
      (node (ref "D8") (pin "47") (pinfunction "PB10_47") (pintype "bidirectional"))
    )
    (net (code "14") (name "/E_RMII_CRSDV") (class "Default")
      (node (ref "D10") (pin "40") (pinfunction "CRS/CRS_DV/LED_CFG_40") (pintype "output"))
      (node (ref "D8") (pin "32") (pinfunction "PA7_32") (pintype "bidirectional"))
      (node (ref "R49") (pin "1") (pinfunction "1_1") (pintype "passive"))
    )
    (net (code "15") (name "/E_RXD0") (class "Default")
      (node (ref "D10") (pin "43") (pinfunction "RXD_0/PHYAD1_43") (pintype "output"))
      (node (ref "D8") (pin "33") (pinfunction "PC4_33") (pintype "bidirectional"))
    )
    (net (code "16") (name "/E_RXD1") (class "Default")
      (node (ref "D10") (pin "44") (pinfunction "RXD_1/PHYAD2_44") (pintype "output"))
      (node (ref "D8") (pin "34") (pinfunction "PC5_34") (pintype "bidirectional"))
    )
    (net (code "17") (name "/E_TXD0") (class "Default")
      (node (ref "D10") (pin "3") (pinfunction "TXD_0_3") (pintype "input"))
      (node (ref "D8") (pin "51") (pinfunction "PB12_51") (pintype "bidirectional"))
    )
    (net (code "18") (name "/E_TXD1") (class "Default")
      (node (ref "D10") (pin "4") (pinfunction "TXD_1_4") (pintype "input"))
      (node (ref "D8") (pin "52") (pinfunction "PB13_52") (pintype "bidirectional"))
    )
    (net (code "19") (name "/E_TXEN") (class "Default")
      (node (ref "D10") (pin "2") (pinfunction "TX_EN_2") (pintype "input"))
      (node (ref "D8") (pin "48") (pinfunction "PB11_48") (pintype "bidirectional"))
    )
    (net (code "20") (name "/FL_CSS") (class "Default")
      (node (ref "D1") (pin "4") (pinfunction "CS_4") (pintype "power_in"))
      (node (ref "D8") (pin "35") (pinfunction "PB0_35") (pintype "bidirectional"))
      (node (ref "R2") (pin "1") (pinfunction "1_1") (pintype "passive"))
    )
    (net (code "21") (name "/I2C1_SCL") (class "Default")
      (node (ref "D8") (pin "95") (pinfunction "PB8_95") (pintype "bidirectional"))
      (node (ref "R67") (pin "1") (pinfunction "1_1") (pintype "passive"))
      (node (ref "X11") (pin "4") (pinfunction "4_4") (pintype "passive"))
    )
    (net (code "22") (name "/I2C1_SDA") (class "Default")
      (node (ref "D8") (pin "96") (pinfunction "PB9_96") (pintype "bidirectional"))
      (node (ref "R60") (pin "1") (pinfunction "1_1") (pintype "passive"))
      (node (ref "X11") (pin "5") (pinfunction "5_5") (pintype "passive"))
    )
    (net (code "23") (name "/JDTI") (class "Default")
      (node (ref "D8") (pin "77") (pinfunction "PA15(JTDI)_77") (pintype "bidirectional"))
      (node (ref "R37") (pin "1") (pinfunction "1_1") (pintype "passive"))
      (node (ref "X9") (pin "7") (pinfunction "7_7") (pintype "passive"))
    )
    (net (code "24") (name "/LED1") (class "Default")
      (node (ref "D8") (pin "3") (pinfunction "PE4_3") (pintype "bidirectional"))
      (node (ref "HL6") (pin "2") (pinfunction "K_2") (pintype "passive"))
    )
    (net (code "25") (name "/LED2") (class "Default")
      (node (ref "D8") (pin "2") (pinfunction "PE3_2") (pintype "bidirectional"))
      (node (ref "HL5") (pin "2") (pinfunction "K_2") (pintype "passive"))
    )
    (net (code "26") (name "/LED3") (class "Default")
      (node (ref "D8") (pin "4") (pinfunction "PE5_4") (pintype "bidirectional"))
      (node (ref "HL4") (pin "2") (pinfunction "K_2") (pintype "passive"))
    )
    (net (code "27") (name "/LED_ACT") (class "Default")
      (node (ref "D10") (pin "26") (pinfunction "LED_ACT/COL/AN_EN_26") (pintype "output"))
      (node (ref "R48") (pin "1") (pinfunction "1_1") (pintype "passive"))
      (node (ref "X12") (pin "11") (pinfunction "RC_11") (pintype "passive"))
    )
    (net (code "28") (name "/LED_LINK") (class "Default")
      (node (ref "D10") (pin "28") (pinfunction "LED_LINK/AN0_28") (pintype "output"))
      (node (ref "R50") (pin "1") (pinfunction "1_1") (pintype "passive"))
      (node (ref "X12") (pin "10") (pinfunction "LC_10") (pintype "passive"))
    )
    (net (code "29") (name "/MISO") (class "Default")
      (node (ref "D1") (pin "8") (pinfunction "SO_8") (pintype "power_in"))
      (node (ref "D2") (pin "2") (pinfunction "Q_2") (pintype "passive"))
      (node (ref "D8") (pin "31") (pinfunction "PA6_31") (pintype "bidirectional"))
      (node (ref "X11") (pin "10") (pinfunction "10_10") (pintype "passive"))
    )
    (net (code "30") (name "/MOSI") (class "Default")
      (node (ref "D1") (pin "1") (pinfunction "SI_1") (pintype "passive"))
      (node (ref "D2") (pin "5") (pinfunction "D_5") (pintype "passive"))
      (node (ref "D8") (pin "91") (pinfunction "PB5_91") (pintype "bidirectional"))
      (node (ref "X11") (pin "7") (pinfunction "7_7") (pintype "passive"))
    )
    (net (code "31") (name "/NJRST") (class "Default")
      (node (ref "D8") (pin "90") (pinfunction "PB4(NJTRST)_90") (pintype "bidirectional"))
      (node (ref "R36") (pin "1") (pinfunction "1_1") (pintype "passive"))
      (node (ref "X9") (pin "5") (pinfunction "5_5") (pintype "passive"))
    )
    (net (code "32") (name "/NRST") (class "Default")
      (node (ref "C36") (pin "1") (pinfunction "1_1") (pintype "passive"))
      (node (ref "D8") (pin "14") (pinfunction "NRST_14") (pintype "bidirectional"))
      (node (ref "R31") (pin "1") (pinfunction "1_1") (pintype "passive"))
      (node (ref "S1") (pin "1") (pinfunction "1_1") (pintype "passive"))
    )
    (net (code "33") (name "/PD3") (class "Default")
      (node (ref "D8") (pin "84") (pinfunction "PD3_84") (pintype "bidirectional"))
      (node (ref "X11") (pin "1") (pinfunction "1_1") (pintype "passive"))
    )
    (net (code "34") (name "/PD4") (class "Default")
      (node (ref "D8") (pin "85") (pinfunction "PD4_85") (pintype "bidirectional"))
      (node (ref "X11") (pin "2") (pinfunction "2_2") (pintype "passive"))
    )
    (net (code "35") (name "/PD7") (class "Default")
      (node (ref "D8") (pin "88") (pinfunction "PD7_88") (pintype "bidirectional"))
      (node (ref "X11") (pin "3") (pinfunction "3_3") (pintype "passive"))
    )
    (net (code "36") (name "/PE0") (class "Default")
      (node (ref "D8") (pin "97") (pinfunction "PE0_97") (pintype "bidirectional"))
      (node (ref "X11") (pin "6") (pinfunction "6_6") (pintype "passive"))
    )
    (net (code "37") (name "/PFB") (class "Default")
      (node (ref "C46") (pin "1") (pinfunction "1_1") (pintype "passive"))
      (node (ref "C47") (pin "1") (pinfunction "1_1") (pintype "passive"))
      (node (ref "C52") (pin "1") (pinfunction "1_1") (pintype "passive"))
      (node (ref "C54") (pin "1") (pinfunction "1_1") (pintype "passive"))
      (node (ref "D10") (pin "18") (pinfunction "PFBIN1_18") (pintype "input"))
      (node (ref "D10") (pin "23") (pinfunction "PFBOUT_23") (pintype "output"))
      (node (ref "D10") (pin "37") (pinfunction "PFBIN2_37") (pintype "input"))
    )
    (net (code "38") (name "/RD_N") (class "Default")
      (node (ref "D10") (pin "13") (pinfunction "RD-_13") (pintype "bidirectional"))
      (node (ref "R65") (pin "1") (pinfunction "1_1") (pintype "passive"))
      (node (ref "VD8") (pin "5") (pinfunction "D_5") (pintype "passive"))
      (node (ref "X12") (pin "6") (pinfunction "RD-_6") (pintype "passive"))
    )
    (net (code "39") (name "/RD_P") (class "Default")
      (node (ref "D10") (pin "14") (pinfunction "RD+_14") (pintype "bidirectional"))
      (node (ref "R63") (pin "1") (pinfunction "1_1") (pintype "passive"))
      (node (ref "VD8") (pin "4") (pinfunction "B_4") (pintype "passive"))
      (node (ref "X12") (pin "3") (pinfunction "RD+_3") (pintype "passive"))
    )
    (net (code "40") (name "/RS485_Cntr") (class "Default")
      (node (ref "D6") (pin "2") (pinfunction "RE_2") (pintype "passive"))
      (node (ref "D6") (pin "3") (pinfunction "DE_3") (pintype "passive"))
      (node (ref "D8") (pin "1") (pinfunction "PE2_1") (pintype "bidirectional"))
      (node (ref "R11") (pin "2") (pinfunction "2_2") (pintype "passive"))
    )
    (net (code "41") (name "/RS485_N") (class "Default")
      (node (ref "D6") (pin "6") (pinfunction "A_6") (pintype "passive"))
      (node (ref "R22") (pin "2") (pinfunction "2_2") (pintype "passive"))
      (node (ref "X6") (pin "2") (pinfunction "2_2") (pintype "passive"))
      (node (ref "X7") (pin "4") (pinfunction "4_4") (pintype "passive"))
    )
    (net (code "42") (name "/RS485_P") (class "Default")
      (node (ref "D6") (pin "7") (pinfunction "B_7") (pintype "passive"))
      (node (ref "D9") (pin "13") (pinfunction "R1IN_13") (pintype "passive"))
      (node (ref "R20") (pin "1") (pinfunction "1_1") (pintype "passive"))
      (node (ref "R21") (pin "2") (pinfunction "2_2") (pintype "passive"))
      (node (ref "X7") (pin "3") (pinfunction "3_3") (pintype "passive"))
    )
    (net (code "43") (name "/RX2") (class "Default")
      (node (ref "D6") (pin "1") (pinfunction "RO_1") (pintype "passive"))
      (node (ref "D8") (pin "87") (pinfunction "PD6_87") (pintype "bidirectional"))
      (node (ref "D9") (pin "12") (pinfunction "R1OUT_12") (pintype "passive"))
      (node (ref "R10") (pin "1") (pinfunction "1_1") (pintype "passive"))
    )
    (net (code "44") (name "/SCK") (class "Default")
      (node (ref "D1") (pin "2") (pinfunction "SCK_2") (pintype "passive"))
      (node (ref "D2") (pin "6") (pinfunction "C_6") (pintype "passive"))
      (node (ref "D8") (pin "30") (pinfunction "PA5_30") (pintype "bidirectional"))
      (node (ref "R5") (pin "2") (pinfunction "2_2") (pintype "passive"))
      (node (ref "X11") (pin "9") (pinfunction "9_9") (pintype "passive"))
    )
    (net (code "45") (name "/SDIO_CLK") (class "Default")
      (node (ref "D8") (pin "80") (pinfunction "PC12_80") (pintype "bidirectional"))
      (node (ref "R18") (pin "1") (pinfunction "1_1") (pintype "passive"))
      (node (ref "X4") (pin "5") (pinfunction "CLK_5") (pintype "passive"))
    )
    (net (code "46") (name "/SDIO_CMD") (class "Default")
      (node (ref "D8") (pin "83") (pinfunction "PD2_83") (pintype "bidirectional"))
      (node (ref "R17") (pin "1") (pinfunction "1_1") (pintype "passive"))
      (node (ref "X4") (pin "3") (pinfunction "CMD_3") (pintype "passive"))
    )
    (net (code "47") (name "/SDIO_D0") (class "Default")
      (node (ref "D8") (pin "65") (pinfunction "PC8_65") (pintype "bidirectional"))
      (node (ref "R12") (pin "1") (pinfunction "1_1") (pintype "passive"))
      (node (ref "X4") (pin "7") (pinfunction "D0_7") (pintype "passive"))
    )
    (net (code "48") (name "/SDIO_D1") (class "Default")
      (node (ref "D8") (pin "66") (pinfunction "PC9_66") (pintype "bidirectional"))
      (node (ref "R13") (pin "1") (pinfunction "1_1") (pintype "passive"))
      (node (ref "X4") (pin "8") (pinfunction "D1_8") (pintype "passive"))
    )
    (net (code "49") (name "/SDIO_D2") (class "Default")
      (node (ref "D8") (pin "78") (pinfunction "PC10_78") (pintype "bidirectional"))
      (node (ref "R14") (pin "1") (pinfunction "1_1") (pintype "passive"))
      (node (ref "X4") (pin "1") (pinfunction "D2_1") (pintype "passive"))
    )
    (net (code "50") (name "/SDIO_D3") (class "Default")
      (node (ref "D8") (pin "79") (pinfunction "PC11_79") (pintype "bidirectional"))
      (node (ref "R15") (pin "1") (pinfunction "1_1") (pintype "passive"))
      (node (ref "X4") (pin "2") (pinfunction "D3_2") (pintype "passive"))
    )
    (net (code "51") (name "/SWCLK") (class "Default")
      (node (ref "D8") (pin "76") (pinfunction "PA14(JTCK-SWCLK)_76") (pintype "bidirectional"))
      (node (ref "R41") (pin "2") (pinfunction "2_2") (pintype "passive"))
      (node (ref "X9") (pin "4") (pinfunction "4_4") (pintype "passive"))
    )
    (net (code "52") (name "/SWDIO") (class "Default")
      (node (ref "D8") (pin "72") (pinfunction "PA13(JTMS-SWDIO)_72") (pintype "bidirectional"))
      (node (ref "R38") (pin "1") (pinfunction "1_1") (pintype "passive"))
      (node (ref "X9") (pin "2") (pinfunction "2_2") (pintype "passive"))
    )
    (net (code "53") (name "/SWITCH1") (class "Default")
      (node (ref "D8") (pin "64") (pinfunction "PC7_64") (pintype "bidirectional"))
      (node (ref "R54") (pin "1") (pinfunction "1_1") (pintype "passive"))
      (node (ref "S2") (pin "1") (pinfunction "1_1") (pintype "passive"))
    )
    (net (code "54") (name "/SWITCH2") (class "Default")
      (node (ref "D8") (pin "63") (pinfunction "PC6_63") (pintype "bidirectional"))
      (node (ref "R55") (pin "1") (pinfunction "1_1") (pintype "passive"))
      (node (ref "S2") (pin "2") (pinfunction "2_2") (pintype "passive"))
    )
    (net (code "55") (name "/SWITCH3") (class "Default")
      (node (ref "D8") (pin "62") (pinfunction "PD15_62") (pintype "bidirectional"))
      (node (ref "R56") (pin "1") (pinfunction "1_1") (pintype "passive"))
      (node (ref "S2") (pin "3") (pinfunction "3_3") (pintype "passive"))
    )
    (net (code "56") (name "/SWITCH4") (class "Default")
      (node (ref "D8") (pin "61") (pinfunction "PD14_61") (pintype "bidirectional"))
      (node (ref "R57") (pin "1") (pinfunction "1_1") (pintype "passive"))
      (node (ref "S2") (pin "4") (pinfunction "4_4") (pintype "passive"))
    )
    (net (code "57") (name "/SWITCH5") (class "Default")
      (node (ref "D8") (pin "60") (pinfunction "PD13_60") (pintype "bidirectional"))
      (node (ref "R59") (pin "1") (pinfunction "1_1") (pintype "passive"))
      (node (ref "S2") (pin "5") (pinfunction "5_5") (pintype "passive"))
    )
    (net (code "58") (name "/SWITCH6") (class "Default")
      (node (ref "D8") (pin "59") (pinfunction "PD12_59") (pintype "bidirectional"))
      (node (ref "R62") (pin "1") (pinfunction "1_1") (pintype "passive"))
      (node (ref "S2") (pin "6") (pinfunction "6_6") (pintype "passive"))
    )
    (net (code "59") (name "/SWITCH7") (class "Default")
      (node (ref "D8") (pin "58") (pinfunction "PD11_58") (pintype "bidirectional"))
      (node (ref "R64") (pin "1") (pinfunction "1_1") (pintype "passive"))
      (node (ref "S2") (pin "7") (pinfunction "7_7") (pintype "passive"))
    )
    (net (code "60") (name "/SWITCH8") (class "Default")
      (node (ref "D8") (pin "57") (pinfunction "PD10_57") (pintype "bidirectional"))
      (node (ref "R66") (pin "1") (pinfunction "1_1") (pintype "passive"))
      (node (ref "S2") (pin "8") (pinfunction "8_8") (pintype "passive"))
    )
    (net (code "61") (name "/SWO") (class "Default")
      (node (ref "D8") (pin "89") (pinfunction "PB3(JTDO/TRACESWO)_89") (pintype "bidirectional"))
      (node (ref "R40") (pin "1") (pinfunction "1_1") (pintype "passive"))
      (node (ref "X9") (pin "6") (pinfunction "6_6") (pintype "passive"))
    )
    (net (code "62") (name "/TD_N") (class "Default")
      (node (ref "D10") (pin "16") (pinfunction "TD-_16") (pintype "bidirectional"))
      (node (ref "R61") (pin "1") (pinfunction "1_1") (pintype "passive"))
      (node (ref "VD8") (pin "3") (pinfunction "C_3") (pintype "passive"))
      (node (ref "X12") (pin "2") (pinfunction "TD-_2") (pintype "passive"))
    )
    (net (code "63") (name "/TD_P") (class "Default")
      (node (ref "D10") (pin "17") (pinfunction "TD+_17") (pintype "bidirectional"))
      (node (ref "R58") (pin "1") (pinfunction "1_1") (pintype "passive"))
      (node (ref "VD8") (pin "1") (pinfunction "A_1") (pintype "passive"))
      (node (ref "X12") (pin "1") (pinfunction "TD+_1") (pintype "passive"))
    )
    (net (code "64") (name "/TX2") (class "Default")
      (node (ref "D6") (pin "4") (pinfunction "DI_4") (pintype "power_in"))
      (node (ref "D8") (pin "86") (pinfunction "PD5_86") (pintype "bidirectional"))
      (node (ref "D9") (pin "11") (pinfunction "T1IN_11") (pintype "passive"))
    )
    (net (code "65") (name "/TxD") (class "Default")
      (node (ref "D9") (pin "14") (pinfunction "T1OUT_14") (pintype "passive"))
      (node (ref "X7") (pin "2") (pinfunction "2_2") (pintype "passive"))
    )
    (net (code "66") (name "/USART1_Rx") (class "Default")
      (node (ref "D4") (pin "1") (pinfunction "TXD_1") (pintype "output"))
      (node (ref "D8") (pin "69") (pinfunction "PA10_69") (pintype "bidirectional"))
      (node (ref "R16") (pin "1") (pinfunction "1_1") (pintype "passive"))
    )
    (net (code "67") (name "/USART1_Tx") (class "Default")
      (node (ref "D4") (pin "4") (pinfunction "RXD_4") (pintype "input"))
      (node (ref "D8") (pin "68") (pinfunction "PA9_68") (pintype "bidirectional"))
      (node (ref "R19") (pin "1") (pinfunction "1_1") (pintype "passive"))
    )
    (net (code "68") (name "/USART3_Rx") (class "Default")
      (node (ref "D8") (pin "56") (pinfunction "PD9_56") (pintype "bidirectional"))
      (node (ref "X10") (pin "3") (pinfunction "3_3") (pintype "passive"))
    )
    (net (code "69") (name "/USART3_Tx") (class "Default")
      (node (ref "D8") (pin "55") (pinfunction "PD8_55") (pintype "bidirectional"))
      (node (ref "X10") (pin "2") (pinfunction "2_2") (pintype "passive"))
    )
    (net (code "70") (name "/USB_N") (class "Default")
      (node (ref "C5") (pin "2") (pinfunction "2_2") (pintype "passive"))
      (node (ref "D4") (pin "9") (pinfunction "USBDM_9") (pintype "input"))
      (node (ref "R7") (pin "1") (pinfunction "1_1") (pintype "passive"))
      (node (ref "R7") (pin "2") (pinfunction "2_2") (pintype "passive"))
      (node (ref "VD2") (pin "3") (pinfunction "B_3") (pintype "passive"))
      (node (ref "X1") (pin "2") (pinfunction "D-_2") (pintype "passive"))
    )
    (net (code "71") (name "/USB_P") (class "Default")
      (node (ref "C4") (pin "2") (pinfunction "2_2") (pintype "passive"))
      (node (ref "D4") (pin "8") (pinfunction "USBDP_8") (pintype "input"))
      (node (ref "R6") (pin "1") (pinfunction "1_1") (pintype "passive"))
      (node (ref "R6") (pin "2") (pinfunction "2_2") (pintype "passive"))
      (node (ref "VD2") (pin "4") (pinfunction "C_4") (pintype "passive"))
      (node (ref "X1") (pin "3") (pinfunction "D+_3") (pintype "passive"))
    )
    (net (code "72") (name "/nHOLD") (class "Default")
      (node (ref "D2") (pin "7") (pinfunction "HOLD_7") (pintype "passive"))
      (node (ref "D8") (pin "29") (pinfunction "PA4_29") (pintype "bidirectional"))
    )
    (net (code "73") (name "/nW") (class "Default")
      (node (ref "D2") (pin "3") (pinfunction "W_3") (pintype "passive"))
      (node (ref "D8") (pin "38") (pinfunction "PE7_38") (pintype "bidirectional"))
    )
    (net (code "74") (name "3V3") (class "Default")
      (node (ref "BQ3") (pin "4") (pinfunction "+VS_4") (pintype "passive"))
      (node (ref "C10") (pin "1") (pinfunction "1_1") (pintype "passive"))
      (node (ref "C11") (pin "1") (pinfunction "1_1") (pintype "passive"))
      (node (ref "C19") (pin "1") (pinfunction "1_1") (pintype "passive"))
      (node (ref "C2") (pin "2") (pinfunction "2_2") (pintype "passive"))
      (node (ref "C20") (pin "2") (pinfunction "2_2") (pintype "passive"))
      (node (ref "C21") (pin "2") (pinfunction "2_2") (pintype "passive"))
      (node (ref "C22") (pin "2") (pinfunction "2_2") (pintype "passive"))
      (node (ref "C23") (pin "1") (pinfunction "1_1") (pintype "passive"))
      (node (ref "C24") (pin "2") (pinfunction "2_2") (pintype "passive"))
      (node (ref "C27") (pin "2") (pinfunction "2_2") (pintype "passive"))
      (node (ref "C28") (pin "2") (pinfunction "2_2") (pintype "passive"))
      (node (ref "C3") (pin "1") (pinfunction "1_1") (pintype "passive"))
      (node (ref "C33") (pin "2") (pinfunction "2_2") (pintype "passive"))
      (node (ref "C39") (pin "1") (pinfunction "1_1") (pintype "passive"))
      (node (ref "C40") (pin "1") (pinfunction "1_1") (pintype "passive"))
      (node (ref "C41") (pin "1") (pinfunction "1_1") (pintype "passive"))
      (node (ref "C42") (pin "1") (pinfunction "1_1") (pintype "passive"))
      (node (ref "C43") (pin "2") (pinfunction "2_2") (pintype "passive"))
      (node (ref "C45") (pin "2") (pinfunction "2_2") (pintype "passive"))
      (node (ref "C48") (pin "2") (pinfunction "2_2") (pintype "passive"))
      (node (ref "C49") (pin "2") (pinfunction "2_2") (pintype "passive"))
      (node (ref "C50") (pin "1") (pinfunction "1_1") (pintype "passive"))
      (node (ref "C51") (pin "1") (pinfunction "1_1") (pintype "passive"))
      (node (ref "C8") (pin "2") (pinfunction "2_2") (pintype "passive"))
      (node (ref "D1") (pin "3") (pinfunction "RESET_3") (pintype "passive"))
      (node (ref "D1") (pin "5") (pinfunction "WP_5") (pintype "passive"))
      (node (ref "D1") (pin "6") (pinfunction "VCC_6") (pintype "passive"))
      (node (ref "D10") (pin "22") (pinfunction "AVDD33_22") (pintype "power_in"))
      (node (ref "D10") (pin "32") (pinfunction "IOVDD33_2_32") (pintype "power_in"))
      (node (ref "D10") (pin "48") (pinfunction "IOVDD33_48") (pintype "power_in"))
      (node (ref "D2") (pin "8") (pinfunction "VCC_8") (pintype "power_in"))
      (node (ref "D3") (pin "3") (pinfunction "VCC_3") (pintype "power_in"))
      (node (ref "D6") (pin "8") (pinfunction "VCC_8") (pintype "power_in"))
      (node (ref "D7") (pin "2") (pinfunction "UOUT_2") (pintype "output"))
      (node (ref "D7") (pin "4") (pinfunction "UOUT_4") (pintype "output"))
      (node (ref "D8") (pin "100") (pinfunction "VDD_100") (pintype "power_in"))
      (node (ref "D8") (pin "11") (pinfunction "VDD_11") (pintype "power_in"))
      (node (ref "D8") (pin "19") (pinfunction "VDD_19") (pintype "power_in"))
      (node (ref "D8") (pin "28") (pinfunction "VDD_28") (pintype "power_in"))
      (node (ref "D8") (pin "50") (pinfunction "VDD_50") (pintype "power_in"))
      (node (ref "D8") (pin "75") (pinfunction "VDD_75") (pintype "power_in"))
      (node (ref "D9") (pin "16") (pinfunction "VCC_16") (pintype "power_in"))
      (node (ref "L2") (pin "1") (pinfunction "1_1") (pintype "passive"))
      (node (ref "R1") (pin "2") (pinfunction "2_2") (pintype "passive"))
      (node (ref "R10") (pin "2") (pinfunction "2_2") (pintype "passive"))
      (node (ref "R12") (pin "2") (pinfunction "2_2") (pintype "passive"))
      (node (ref "R13") (pin "2") (pinfunction "2_2") (pintype "passive"))
      (node (ref "R14") (pin "2") (pinfunction "2_2") (pintype "passive"))
      (node (ref "R15") (pin "2") (pinfunction "2_2") (pintype "passive"))
      (node (ref "R17") (pin "2") (pinfunction "2_2") (pintype "passive"))
      (node (ref "R18") (pin "2") (pinfunction "2_2") (pintype "passive"))
      (node (ref "R2") (pin "2") (pinfunction "2_2") (pintype "passive"))
      (node (ref "R22") (pin "1") (pinfunction "1_1") (pintype "passive"))
      (node (ref "R31") (pin "2") (pinfunction "2_2") (pintype "passive"))
      (node (ref "R32") (pin "1") (pinfunction "1_1") (pintype "passive"))
      (node (ref "R33") (pin "1") (pinfunction "1_1") (pintype "passive"))
      (node (ref "R34") (pin "1") (pinfunction "1_1") (pintype "passive"))
      (node (ref "R35") (pin "2") (pinfunction "2_2") (pintype "passive"))
      (node (ref "R36") (pin "2") (pinfunction "2_2") (pintype "passive"))
      (node (ref "R37") (pin "2") (pinfunction "2_2") (pintype "passive"))
      (node (ref "R38") (pin "2") (pinfunction "2_2") (pintype "passive"))
      (node (ref "R40") (pin "2") (pinfunction "2_2") (pintype "passive"))
      (node (ref "R42") (pin "2") (pinfunction "2_2") (pintype "passive"))
      (node (ref "R43") (pin "2") (pinfunction "2_2") (pintype "passive"))
      (node (ref "R45") (pin "2") (pinfunction "2_2") (pintype "passive"))
      (node (ref "R46") (pin "2") (pinfunction "2_2") (pintype "passive"))
      (node (ref "R47") (pin "2") (pinfunction "2_2") (pintype "passive"))
      (node (ref "R48") (pin "2") (pinfunction "2_2") (pintype "passive"))
      (node (ref "R49") (pin "2") (pinfunction "2_2") (pintype "passive"))
      (node (ref "R50") (pin "2") (pinfunction "2_2") (pintype "passive"))
      (node (ref "R52") (pin "2") (pinfunction "2_2") (pintype "passive"))
      (node (ref "R54") (pin "2") (pinfunction "2_2") (pintype "passive"))
      (node (ref "R55") (pin "2") (pinfunction "2_2") (pintype "passive"))
      (node (ref "R56") (pin "2") (pinfunction "2_2") (pintype "passive"))
      (node (ref "R57") (pin "2") (pinfunction "2_2") (pintype "passive"))
      (node (ref "R58") (pin "2") (pinfunction "2_2") (pintype "passive"))
      (node (ref "R59") (pin "2") (pinfunction "2_2") (pintype "passive"))
      (node (ref "R60") (pin "2") (pinfunction "2_2") (pintype "passive"))
      (node (ref "R61") (pin "2") (pinfunction "2_2") (pintype "passive"))
      (node (ref "R62") (pin "2") (pinfunction "2_2") (pintype "passive"))
      (node (ref "R63") (pin "2") (pinfunction "2_2") (pintype "passive"))
      (node (ref "R64") (pin "2") (pinfunction "2_2") (pintype "passive"))
      (node (ref "R65") (pin "2") (pinfunction "2_2") (pintype "passive"))
      (node (ref "R66") (pin "2") (pinfunction "2_2") (pintype "passive"))
      (node (ref "R67") (pin "2") (pinfunction "2_2") (pintype "passive"))
      (node (ref "R69") (pin "2") (pinfunction "2_2") (pintype "passive"))
      (node (ref "R70") (pin "2") (pinfunction "2_2") (pintype "passive"))
      (node (ref "VD7") (pin "2") (pinfunction "A2_2") (pintype "passive"))
      (node (ref "X11") (pin "11") (pinfunction "11_11") (pintype "passive"))
      (node (ref "X11") (pin "12") (pinfunction "12_12") (pintype "passive"))
      (node (ref "X12") (pin "4") (pinfunction "CTT_4") (pintype "passive"))
      (node (ref "X12") (pin "5") (pinfunction "CTR_5") (pintype "passive"))
      (node (ref "X4") (pin "4") (pinfunction "3V3_4") (pintype "passive"))
      (node (ref "X5") (pin "1") (pinfunction "1_1") (pintype "passive"))
      (node (ref "X7") (pin "1") (pinfunction "1_1") (pintype "passive"))
      (node (ref "X8") (pin "1") (pinfunction "1_1") (pintype "passive"))
      (node (ref "X8") (pin "2") (pinfunction "2_2") (pintype "passive"))
      (node (ref "X9") (pin "1") (pinfunction "1_1") (pintype "passive"))
      (node (ref "X9") (pin "3") (pinfunction "3_3") (pintype "passive"))
    )
    (net (code "75") (name "5V") (class "Default")
      (node (ref "C12") (pin "2") (pinfunction "2_2") (pintype "passive"))
      (node (ref "C13") (pin "1") (pinfunction "+_1") (pintype "passive"))
      (node (ref "C14") (pin "2") (pinfunction "2_2") (pintype "passive"))
      (node (ref "C44") (pin "2") (pinfunction "2_2") (pintype "passive"))
      (node (ref "D7") (pin "3") (pinfunction "VIN_3") (pintype "bidirectional"))
      (node (ref "G1") (pin "+") (pinfunction "+_+") (pintype "passive"))
      (node (ref "L1") (pin "2") (pinfunction "2_2") (pintype "passive"))
      (node (ref "R26") (pin "2") (pinfunction "2_2") (pintype "passive"))
      (node (ref "VD4") (pin "C") (pinfunction "C_C") (pintype "passive"))
      (node (ref "X10") (pin "4") (pinfunction "4_4") (pintype "passive"))
      (node (ref "X11") (pin "13") (pinfunction "13_13") (pintype "passive"))
      (node (ref "X11") (pin "14") (pinfunction "14_14") (pintype "passive"))
      (node (ref "X5") (pin "9") (pinfunction "9_9") (pintype "passive"))
      (node (ref "X7") (pin "9") (pinfunction "9_9") (pintype "passive"))
    )
    (net (code "76") (name "GND") (class "Default")
      (node (ref "BQ3") (pin "2") (pinfunction "GND_2") (pintype "passive"))
      (node (ref "C1") (pin "1") (pinfunction "1_1") (pintype "passive"))
      (node (ref "C10") (pin "2") (pinfunction "2_2") (pintype "passive"))
      (node (ref "C11") (pin "2") (pinfunction "2_2") (pintype "passive"))
      (node (ref "C12") (pin "1") (pinfunction "1_1") (pintype "passive"))
      (node (ref "C13") (pin "2") (pinfunction "-_2") (pintype "passive"))
      (node (ref "C14") (pin "1") (pinfunction "1_1") (pintype "passive"))
      (node (ref "C15") (pin "2") (pinfunction "2_2") (pintype "passive"))
      (node (ref "C16") (pin "2") (pinfunction "2_2") (pintype "passive"))
      (node (ref "C19") (pin "2") (pinfunction "2_2") (pintype "passive"))
      (node (ref "C2") (pin "1") (pinfunction "1_1") (pintype "passive"))
      (node (ref "C21") (pin "1") (pinfunction "1_1") (pintype "passive"))
      (node (ref "C22") (pin "1") (pinfunction "1_1") (pintype "passive"))
      (node (ref "C23") (pin "2") (pinfunction "2_2") (pintype "passive"))
      (node (ref "C24") (pin "1") (pinfunction "1_1") (pintype "passive"))
      (node (ref "C25") (pin "2") (pinfunction "2_2") (pintype "passive"))
      (node (ref "C26") (pin "2") (pinfunction "2_2") (pintype "passive"))
      (node (ref "C27") (pin "1") (pinfunction "1_1") (pintype "passive"))
      (node (ref "C28") (pin "1") (pinfunction "1_1") (pintype "passive"))
      (node (ref "C29") (pin "1") (pinfunction "1_1") (pintype "passive"))
      (node (ref "C3") (pin "2") (pinfunction "2_2") (pintype "passive"))
      (node (ref "C30") (pin "2") (pinfunction "2_2") (pintype "passive"))
      (node (ref "C31") (pin "1") (pinfunction "1_1") (pintype "passive"))
      (node (ref "C32") (pin "1") (pinfunction "1_1") (pintype "passive"))
      (node (ref "C33") (pin "1") (pinfunction "1_1") (pintype "passive"))
      (node (ref "C34") (pin "1") (pinfunction "1_1") (pintype "passive"))
      (node (ref "C35") (pin "1") (pinfunction "1_1") (pintype "passive"))
      (node (ref "C36") (pin "2") (pinfunction "2_2") (pintype "passive"))
      (node (ref "C37") (pin "1") (pinfunction "1_1") (pintype "passive"))
      (node (ref "C38") (pin "2") (pinfunction "2_2") (pintype "passive"))
      (node (ref "C39") (pin "2") (pinfunction "2_2") (pintype "passive"))
      (node (ref "C4") (pin "1") (pinfunction "1_1") (pintype "passive"))
      (node (ref "C40") (pin "2") (pinfunction "2_2") (pintype "passive"))
      (node (ref "C41") (pin "2") (pinfunction "2_2") (pintype "passive"))
      (node (ref "C42") (pin "2") (pinfunction "2_2") (pintype "passive"))
      (node (ref "C43") (pin "1") (pinfunction "1_1") (pintype "passive"))
      (node (ref "C44") (pin "1") (pinfunction "1_1") (pintype "passive"))
      (node (ref "C45") (pin "1") (pinfunction "1_1") (pintype "passive"))
      (node (ref "C46") (pin "2") (pinfunction "2_2") (pintype "passive"))
      (node (ref "C47") (pin "2") (pinfunction "2_2") (pintype "passive"))
      (node (ref "C48") (pin "1") (pinfunction "1_1") (pintype "passive"))
      (node (ref "C49") (pin "1") (pinfunction "1_1") (pintype "passive"))
      (node (ref "C5") (pin "1") (pinfunction "1_1") (pintype "passive"))
      (node (ref "C50") (pin "2") (pinfunction "2_2") (pintype "passive"))
      (node (ref "C51") (pin "2") (pinfunction "2_2") (pintype "passive"))
      (node (ref "C52") (pin "2") (pinfunction "2_2") (pintype "passive"))
      (node (ref "C53") (pin "1") (pinfunction "1_1") (pintype "passive"))
      (node (ref "C54") (pin "2") (pinfunction "2_2") (pintype "passive"))
      (node (ref "C6") (pin "1") (pinfunction "1_1") (pintype "passive"))
      (node (ref "C7") (pin "2") (pinfunction "-_2") (pintype "passive"))
      (node (ref "C8") (pin "1") (pinfunction "1_1") (pintype "passive"))
      (node (ref "C9") (pin "1") (pinfunction "1_1") (pintype "passive"))
      (node (ref "D1") (pin "7") (pinfunction "GND_7") (pintype "passive"))
      (node (ref "D10") (pin "15") (pinfunction "AGND_2_15") (pintype "passive"))
      (node (ref "D10") (pin "19") (pinfunction "AGND_19") (pintype "passive"))
      (node (ref "D10") (pin "35") (pinfunction "IOGND_2_35") (pintype "passive"))
      (node (ref "D10") (pin "36") (pinfunction "DGND_36") (pintype "passive"))
      (node (ref "D10") (pin "47") (pinfunction "IOGND_47") (pintype "passive"))
      (node (ref "D10") (pin "49") (pinfunction "EPAD_49") (pintype "passive"))
      (node (ref "D2") (pin "4") (pinfunction "VSS_4") (pintype "power_in"))
      (node (ref "D3") (pin "2") (pinfunction "GND_2") (pintype "power_in"))
      (node (ref "D4") (pin "13") (pinfunction "GND@1_13") (pintype "power_in"))
      (node (ref "D4") (pin "5") (pinfunction "GND_5") (pintype "power_in"))
      (node (ref "D5") (pin "3") (pinfunction "GND_2_3") (pintype "passive"))
      (node (ref "D5") (pin "5") (pinfunction "~{ON}/OFF_5") (pintype "input"))
      (node (ref "D5") (pin "6") (pinfunction "GND_6") (pintype "passive"))
      (node (ref "D6") (pin "5") (pinfunction "GND_5") (pintype "passive"))
      (node (ref "D7") (pin "1") (pinfunction "GND_1") (pintype "passive"))
      (node (ref "D8") (pin "10") (pinfunction "VSS_10") (pintype "power_in"))
      (node (ref "D8") (pin "20") (pinfunction "VSSA_20") (pintype "power_in"))
      (node (ref "D8") (pin "27") (pinfunction "VSS_27") (pintype "power_in"))
      (node (ref "D8") (pin "74") (pinfunction "VSS_74") (pintype "power_in"))
      (node (ref "D8") (pin "99") (pinfunction "VSS_99") (pintype "power_in"))
      (node (ref "D9") (pin "15") (pinfunction "GND_15") (pintype "passive"))
      (node (ref "HL1") (pin "2") (pinfunction "K_2") (pintype "passive"))
      (node (ref "J1") (pin "3") (pinfunction "NEG_3") (pintype "passive"))
      (node (ref "R11") (pin "1") (pinfunction "1_1") (pintype "passive"))
      (node (ref "R20") (pin "2") (pinfunction "2_2") (pintype "passive"))
      (node (ref "R25") (pin "1") (pinfunction "1_1") (pintype "passive"))
      (node (ref "R41") (pin "1") (pinfunction "1_1") (pintype "passive"))
      (node (ref "R5") (pin "1") (pinfunction "1_1") (pintype "passive"))
      (node (ref "R53") (pin "2") (pinfunction "2_2") (pintype "passive"))
      (node (ref "R68") (pin "1") (pinfunction "1_1") (pintype "passive"))
      (node (ref "S1") (pin "2") (pinfunction "2_2") (pintype "passive"))
      (node (ref "S2") (pin "10") (pinfunction "10_10") (pintype "passive"))
      (node (ref "S2") (pin "11") (pinfunction "11_11") (pintype "passive"))
      (node (ref "S2") (pin "12") (pinfunction "12_12") (pintype "passive"))
      (node (ref "S2") (pin "13") (pinfunction "13_13") (pintype "passive"))
      (node (ref "S2") (pin "14") (pinfunction "14_14") (pintype "passive"))
      (node (ref "S2") (pin "15") (pinfunction "15_15") (pintype "passive"))
      (node (ref "S2") (pin "16") (pinfunction "16_16") (pintype "passive"))
      (node (ref "S2") (pin "9") (pinfunction "9_9") (pintype "passive"))
      (node (ref "VD1") (pin "2") (pinfunction "K_2") (pintype "passive"))
      (node (ref "VD2") (pin "1") (pinfunction "GND_1") (pintype "passive"))
      (node (ref "VD5") (pin "1") (pinfunction "GND_1") (pintype "passive"))
      (node (ref "VD6") (pin "1") (pinfunction "POS_1") (pintype "passive"))
      (node (ref "VD8") (pin "2") (pinfunction "GND_2") (pintype "passive"))
      (node (ref "VT1") (pin "E") (pinfunction "E_E") (pintype "passive"))
      (node (ref "X1") (pin "5") (pinfunction "GND_5") (pintype "passive"))
      (node (ref "X10") (pin "1") (pinfunction "1_1") (pintype "passive"))
      (node (ref "X11") (pin "15") (pinfunction "15_15") (pintype "passive"))
      (node (ref "X11") (pin "16") (pinfunction "16_16") (pintype "passive"))
      (node (ref "X11") (pin "8") (pinfunction "8_8") (pintype "passive"))
      (node (ref "X12") (pin "8") (pinfunction "CG_8") (pintype "passive"))
      (node (ref "X2") (pin "2") (pinfunction "2_2") (pintype "passive"))
      (node (ref "X4") (pin "6") (pinfunction "GND_6") (pintype "passive"))
      (node (ref "X5") (pin "3") (pinfunction "3_3") (pintype "passive"))
      (node (ref "X5") (pin "5") (pinfunction "5_5") (pintype "passive"))
      (node (ref "X7") (pin "5") (pinfunction "5_5") (pintype "passive"))
      (node (ref "X8") (pin "5") (pinfunction "5_5") (pintype "passive"))
      (node (ref "X8") (pin "6") (pinfunction "6_6") (pintype "passive"))
      (node (ref "X9") (pin "8") (pinfunction "8_8") (pintype "passive"))
    )
    (net (code "77") (name "Net-(C7-+)") (class "Default")
      (node (ref "C6") (pin "2") (pinfunction "2_2") (pintype "passive"))
      (node (ref "C7") (pin "1") (pinfunction "+_1") (pintype "passive"))
      (node (ref "D5") (pin "1") (pinfunction "VIN_1") (pintype "power_in"))
      (node (ref "R8") (pin "1") (pinfunction "1_1") (pintype "passive"))
      (node (ref "VD3") (pin "2") (pinfunction "NEG_2") (pintype "passive"))
    )
    (net (code "78") (name "Net-(D3-RS)") (class "Default")
      (node (ref "D3") (pin "8") (pinfunction "RS_8") (pintype "input"))
      (node (ref "R3") (pin "1") (pinfunction "1_1") (pintype "passive"))
    )
    (net (code "79") (name "Net-(D4-CBUS1)") (class "Default")
      (node (ref "D4") (pin "14") (pinfunction "CBUS1_14") (pintype "bidirectional"))
      (node (ref "HL2") (pin "2") (pinfunction "NEG_2") (pintype "passive"))
    )
    (net (code "80") (name "Net-(D4-CBUS2)") (class "Default")
      (node (ref "D4") (pin "7") (pinfunction "CBUS2_7") (pintype "bidirectional"))
      (node (ref "HL3") (pin "2") (pinfunction "NEG_2") (pintype "passive"))
    )
    (net (code "81") (name "Net-(D5-FB)") (class "Default")
      (node (ref "D5") (pin "4") (pinfunction "FB_4") (pintype "input"))
      (node (ref "R25") (pin "2") (pinfunction "2_2") (pintype "passive"))
      (node (ref "R26") (pin "1") (pinfunction "1_1") (pintype "passive"))
    )
    (net (code "82") (name "Net-(D5-OUT)") (class "Default")
      (node (ref "D5") (pin "2") (pinfunction "OUT_2") (pintype "output"))
      (node (ref "L1") (pin "1") (pinfunction "1_1") (pintype "passive"))
      (node (ref "VD6") (pin "2") (pinfunction "NEG_2") (pintype "passive"))
    )
    (net (code "83") (name "Net-(D8A-BOOT0)") (class "Default")
      (node (ref "D8") (pin "94") (pinfunction "BOOT0_94") (pintype "input"))
      (node (ref "R29") (pin "1") (pinfunction "1_1") (pintype "passive"))
    )
    (net (code "84") (name "Net-(D8A-PB2-BOOT1(PB2))") (class "Default")
      (node (ref "D8") (pin "37") (pinfunction "PB2-BOOT1(PB2)_37") (pintype "bidirectional"))
      (node (ref "R28") (pin "1") (pinfunction "1_1") (pintype "passive"))
    )
    (net (code "85") (name "Net-(D8A-PC14-OSC32_IN(PC14))") (class "Default")
      (node (ref "BQ1") (pin "2") (pinfunction "2_2") (pintype "passive"))
      (node (ref "C15") (pin "1") (pinfunction "1_1") (pintype "passive"))
      (node (ref "D8") (pin "8") (pinfunction "PC14-OSC32_IN(PC14)_8") (pintype "bidirectional"))
    )
    (net (code "86") (name "Net-(D8A-PC15-OSC32_OUT(PC15))") (class "Default")
      (node (ref "BQ1") (pin "1") (pinfunction "1_1") (pintype "passive"))
      (node (ref "C16") (pin "1") (pinfunction "1_1") (pintype "passive"))
      (node (ref "D8") (pin "9") (pinfunction "PC15-OSC32_OUT(PC15)_9") (pintype "bidirectional"))
    )
    (net (code "87") (name "Net-(D8A-PH0-OSC_IN(PH0))") (class "Default")
      (node (ref "BQ2") (pin "2") (pinfunction "2_2") (pintype "passive"))
      (node (ref "C37") (pin "2") (pinfunction "2_2") (pintype "passive"))
      (node (ref "D8") (pin "12") (pinfunction "PH0-OSC_IN(PH0)_12") (pintype "bidirectional"))
      (node (ref "R30") (pin "2") (pinfunction "2_2") (pintype "passive"))
    )
    (net (code "88") (name "Net-(D8A-PH1-OSC_OUT(PH1))") (class "Default")
      (node (ref "BQ2") (pin "1") (pinfunction "1_1") (pintype "passive"))
      (node (ref "C38") (pin "1") (pinfunction "1_1") (pintype "passive"))
      (node (ref "D8") (pin "13") (pinfunction "PH1-OSC_OUT(PH1)_13") (pintype "bidirectional"))
      (node (ref "R30") (pin "1") (pinfunction "1_1") (pintype "passive"))
    )
    (net (code "89") (name "Net-(D8A-VCAP_1)") (class "Default")
      (node (ref "C34") (pin "2") (pinfunction "2_2") (pintype "passive"))
      (node (ref "D8") (pin "49") (pinfunction "VCAP_1_49") (pintype "power_in"))
    )
    (net (code "90") (name "Net-(D8A-VCAP_2)") (class "Default")
      (node (ref "C32") (pin "2") (pinfunction "2_2") (pintype "passive"))
      (node (ref "D8") (pin "73") (pinfunction "VCAP_2_73") (pintype "power_in"))
    )
    (net (code "91") (name "Net-(D8B-VBAT)") (class "Default")
      (node (ref "C35") (pin "2") (pinfunction "2_2") (pintype "passive"))
      (node (ref "D8") (pin "6") (pinfunction "VBAT_6") (pintype "power_in"))
      (node (ref "VD7") (pin "3") (pinfunction "C_3") (pintype "passive"))
    )
    (net (code "92") (name "Net-(D8B-VDDA)") (class "Default")
      (node (ref "C26") (pin "1") (pinfunction "1_1") (pintype "passive"))
      (node (ref "C30") (pin "1") (pinfunction "1_1") (pintype "passive"))
      (node (ref "D8") (pin "22") (pinfunction "VDDA_22") (pintype "power_in"))
      (node (ref "L2") (pin "2") (pinfunction "2_2") (pintype "passive"))
      (node (ref "R27") (pin "1") (pinfunction "1_1") (pintype "passive"))
    )
    (net (code "93") (name "Net-(D8B-VREF+)") (class "Default")
      (node (ref "C25") (pin "1") (pinfunction "1_1") (pintype "passive"))
      (node (ref "C29") (pin "2") (pinfunction "2_2") (pintype "passive"))
      (node (ref "D8") (pin "21") (pinfunction "VREF+_21") (pintype "power_in"))
      (node (ref "R27") (pin "2") (pinfunction "2_2") (pintype "passive"))
    )
    (net (code "94") (name "Net-(D9-C1+)") (class "Default")
      (node (ref "C17") (pin "1") (pinfunction "1_1") (pintype "passive"))
      (node (ref "D9") (pin "1") (pinfunction "C1+_1") (pintype "passive"))
    )
    (net (code "95") (name "Net-(D9-C1-)") (class "Default")
      (node (ref "C17") (pin "2") (pinfunction "2_2") (pintype "passive"))
      (node (ref "D9") (pin "3") (pinfunction "C1-_3") (pintype "passive"))
    )
    (net (code "96") (name "Net-(D9-C2+)") (class "Default")
      (node (ref "C18") (pin "1") (pinfunction "1_1") (pintype "passive"))
      (node (ref "D9") (pin "4") (pinfunction "C2+_4") (pintype "passive"))
    )
    (net (code "97") (name "Net-(D9-C2-)") (class "Default")
      (node (ref "C18") (pin "2") (pinfunction "2_2") (pintype "passive"))
      (node (ref "D9") (pin "5") (pinfunction "C2-_5") (pintype "passive"))
    )
    (net (code "98") (name "Net-(D9-V+)") (class "Default")
      (node (ref "C20") (pin "1") (pinfunction "1_1") (pintype "passive"))
      (node (ref "D9") (pin "2") (pinfunction "V+_2") (pintype "power_in"))
    )
    (net (code "99") (name "Net-(D9-V-)") (class "Default")
      (node (ref "C31") (pin "2") (pinfunction "2_2") (pintype "passive"))
      (node (ref "D9") (pin "6") (pinfunction "V-_6") (pintype "power_in"))
    )
    (net (code "100") (name "Net-(D10-COL{slash}PHYAD0)") (class "Default")
      (node (ref "D10") (pin "42") (pinfunction "COL/PHYAD0_42") (pintype "output"))
      (node (ref "R47") (pin "1") (pinfunction "1_1") (pintype "passive"))
    )
    (net (code "101") (name "Net-(D10-LED_SPEED{slash}AN1)") (class "Default")
      (node (ref "D10") (pin "27") (pinfunction "LED_SPEED/AN1_27") (pintype "output"))
      (node (ref "R52") (pin "1") (pinfunction "1_1") (pintype "passive"))
    )
    (net (code "102") (name "Net-(D10-PWR_DOWN{slash}INT)") (class "Default")
      (node (ref "D10") (pin "7") (pinfunction "PWR_DOWN/INT_7") (pintype "input"))
      (node (ref "R35") (pin "1") (pinfunction "1_1") (pintype "passive"))
    )
    (net (code "103") (name "Net-(D10-RBIAS)") (class "Default")
      (node (ref "D10") (pin "24") (pinfunction "RBIAS_24") (pintype "input"))
      (node (ref "R44") (pin "1") (pinfunction "1_1") (pintype "passive"))
    )
    (net (code "104") (name "Net-(D10-RESERVED)") (class "Default")
      (node (ref "D10") (pin "20") (pinfunction "RESERVED_20") (pintype "bidirectional"))
      (node (ref "R43") (pin "1") (pinfunction "1_1") (pintype "passive"))
    )
    (net (code "105") (name "Net-(D10-RESERVED_2)") (class "Default")
      (node (ref "D10") (pin "21") (pinfunction "RESERVED_2_21") (pintype "bidirectional"))
      (node (ref "R42") (pin "1") (pinfunction "1_1") (pintype "passive"))
    )
    (net (code "106") (name "Net-(D10-RX_DV{slash}MII_MODE)") (class "Default")
      (node (ref "D10") (pin "39") (pinfunction "RX_DV/MII_MODE_39") (pintype "output"))
      (node (ref "R46") (pin "1") (pinfunction "1_1") (pintype "passive"))
    )
    (net (code "107") (name "Net-(F1-Pad2)") (class "Default")
      (node (ref "F1") (pin "2") (pinfunction "2_2") (pintype "passive"))
      (node (ref "R4") (pin "1") (pinfunction "1_1") (pintype "passive"))
    )
    (net (code "108") (name "Net-(G1-Pad2)") (class "Default")
      (node (ref "G1") (pin "2") (pinfunction "2_2") (pintype "passive"))
      (node (ref "VT1") (pin "C") (pinfunction "C_C") (pintype "passive"))
    )
    (net (code "109") (name "Net-(HL1-A)") (class "Default")
      (node (ref "HL1") (pin "1") (pinfunction "A_1") (pintype "passive"))
      (node (ref "R8") (pin "2") (pinfunction "2_2") (pintype "passive"))
    )
    (net (code "110") (name "Net-(HL2-POS)") (class "Default")
      (node (ref "HL2") (pin "1") (pinfunction "POS_1") (pintype "passive"))
      (node (ref "R23") (pin "2") (pinfunction "2_2") (pintype "passive"))
    )
    (net (code "111") (name "Net-(HL3-POS)") (class "Default")
      (node (ref "HL3") (pin "1") (pinfunction "POS_1") (pintype "passive"))
      (node (ref "R24") (pin "2") (pinfunction "2_2") (pintype "passive"))
    )
    (net (code "112") (name "Net-(HL4-A)") (class "Default")
      (node (ref "HL4") (pin "1") (pinfunction "A_1") (pintype "passive"))
      (node (ref "R32") (pin "2") (pinfunction "2_2") (pintype "passive"))
    )
    (net (code "113") (name "Net-(HL5-A)") (class "Default")
      (node (ref "HL5") (pin "1") (pinfunction "A_1") (pintype "passive"))
      (node (ref "R33") (pin "2") (pinfunction "2_2") (pintype "passive"))
    )
    (net (code "114") (name "Net-(HL6-A)") (class "Default")
      (node (ref "HL6") (pin "1") (pinfunction "A_1") (pintype "passive"))
      (node (ref "R34") (pin "2") (pinfunction "2_2") (pintype "passive"))
    )
    (net (code "115") (name "Net-(R9-Pad2)") (class "Default")
      (node (ref "R9") (pin "2") (pinfunction "2_2") (pintype "passive"))
      (node (ref "X3") (pin "1") (pinfunction "1_1") (pintype "passive"))
    )
    (net (code "116") (name "Net-(R21-Pad1)") (class "Default")
      (node (ref "R21") (pin "1") (pinfunction "1_1") (pintype "passive"))
      (node (ref "X6") (pin "1") (pinfunction "1_1") (pintype "passive"))
    )
    (net (code "117") (name "Net-(R39-Pad2)") (class "Default")
      (node (ref "R39") (pin "2") (pinfunction "2_2") (pintype "passive"))
      (node (ref "VT1") (pin "B") (pinfunction "B_B") (pintype "passive"))
    )
    (net (code "118") (name "Net-(R44-Pad2)") (class "Default")
      (node (ref "R44") (pin "2") (pinfunction "2_2") (pintype "passive"))
      (node (ref "R51") (pin "1") (pinfunction "1_1") (pintype "passive"))
    )
    (net (code "119") (name "Net-(R51-Pad2)") (class "Default")
      (node (ref "R51") (pin "2") (pinfunction "2_2") (pintype "passive"))
      (node (ref "R53") (pin "1") (pinfunction "1_1") (pintype "passive"))
    )
    (net (code "120") (name "Net-(VD1-A)") (class "Default")
      (node (ref "R4") (pin "2") (pinfunction "2_2") (pintype "passive"))
      (node (ref "VD1") (pin "1") (pinfunction "A_1") (pintype "passive"))
      (node (ref "VD3") (pin "1") (pinfunction "POS_1") (pintype "passive"))
    )
    (net (code "121") (name "Net-(VD2-A)") (class "Default")
      (node (ref "F2") (pin "1") (pinfunction "1_1") (pintype "passive"))
      (node (ref "VD2") (pin "2") (pinfunction "A_2") (pintype "passive"))
      (node (ref "X1") (pin "1") (pinfunction "VBUS_1") (pintype "passive"))
    )
    (net (code "122") (name "Net-(VD7-A1)") (class "Default")
      (node (ref "J1") (pin "1") (pinfunction "POS_1") (pintype "passive"))
      (node (ref "J1") (pin "2") (pinfunction "POS_2") (pintype "passive"))
      (node (ref "VD7") (pin "1") (pinfunction "A1_1") (pintype "passive"))
    )
    (net (code "123") (name "Net-(X12-LA)") (class "Default")
      (node (ref "R69") (pin "1") (pinfunction "1_1") (pintype "passive"))
      (node (ref "X12") (pin "9") (pinfunction "LA_9") (pintype "passive"))
    )
    (net (code "124") (name "Net-(X12-RA)") (class "Default")
      (node (ref "R70") (pin "1") (pinfunction "1_1") (pintype "passive"))
      (node (ref "X12") (pin "12") (pinfunction "RA_12") (pintype "passive"))
    )
    (net (code "125") (name "SHLD") (class "Default")
      (node (ref "C53") (pin "2") (pinfunction "2_2") (pintype "passive"))
      (node (ref "R68") (pin "2") (pinfunction "2_2") (pintype "passive"))
      (node (ref "X1") (pin "6") (pinfunction "SH_6") (pintype "passive"))
      (node (ref "X1") (pin "7") (pinfunction "SH_7") (pintype "passive"))
      (node (ref "X1") (pin "8") (pinfunction "SH_8") (pintype "passive"))
      (node (ref "X1") (pin "9") (pinfunction "SH_9") (pintype "passive"))
      (node (ref "X12") (pin "S1") (pinfunction "S1_S1") (pintype "passive"))
      (node (ref "X12") (pin "S2") (pinfunction "S2_S2") (pintype "passive"))
      (node (ref "X4") (pin "10") (pinfunction "SHLD_10") (pintype "passive"))
      (node (ref "X4") (pin "11") (pinfunction "SHLD_11") (pintype "passive"))
      (node (ref "X4") (pin "12") (pinfunction "SHLD_12") (pintype "passive"))
      (node (ref "X4") (pin "9") (pinfunction "SHLD_9") (pintype "passive"))
      (node (ref "X5") (pin "10") (pinfunction "MH1_10") (pintype "passive"))
      (node (ref "X5") (pin "11") (pinfunction "MH2_11") (pintype "passive"))
      (node (ref "X7") (pin "10") (pinfunction "MH1_10") (pintype "passive"))
      (node (ref "X7") (pin "11") (pinfunction "MH2_11") (pintype "passive"))
    )
    (net (code "126") (name "VBUS") (class "Default")
      (node (ref "C1") (pin "2") (pinfunction "2_2") (pintype "passive"))
      (node (ref "D4") (pin "12") (pinfunction "VCC_12") (pintype "power_in"))
      (node (ref "F2") (pin "2") (pinfunction "2_2") (pintype "passive"))
      (node (ref "VD4") (pin "A") (pinfunction "A_A") (pintype "passive"))
    )
    (net (code "127") (name "VCC") (class "Default")
      (node (ref "F1") (pin "1") (pinfunction "1_1") (pintype "passive"))
      (node (ref "X2") (pin "1") (pinfunction "1_1") (pintype "passive"))
    )
    (net (code "128") (name "VCCIO") (class "Default")
      (node (ref "C9") (pin "2") (pinfunction "2_2") (pintype "passive"))
      (node (ref "D4") (pin "10") (pinfunction "3V3OUT_10") (pintype "output"))
      (node (ref "D4") (pin "11") (pinfunction "~{RESET}_11") (pintype "input"))
      (node (ref "D4") (pin "3") (pinfunction "VCCIO_3") (pintype "power_in"))
      (node (ref "R16") (pin "2") (pinfunction "2_2") (pintype "passive"))
      (node (ref "R19") (pin "2") (pinfunction "2_2") (pintype "passive"))
      (node (ref "R23") (pin "1") (pinfunction "1_1") (pintype "passive"))
      (node (ref "R24") (pin "1") (pinfunction "1_1") (pintype "passive"))
    )
    (net (code "129") (name "unconnected-(BQ3-STD_OP-Pad1)") (class "Default")
      (node (ref "BQ3") (pin "1") (pinfunction "STD_OP_1") (pintype "passive"))
    )
    (net (code "130") (name "unconnected-(D3-VREF-Pad5)") (class "Default")
      (node (ref "D3") (pin "5") (pinfunction "VREF_5") (pintype "output"))
    )
    (net (code "131") (name "unconnected-(D4-CBUS0-Pad15)") (class "Default")
      (node (ref "D4") (pin "15") (pinfunction "CBUS0_15") (pintype "bidirectional"))
    )
    (net (code "132") (name "unconnected-(D4-CBUS3-Pad16)") (class "Default")
      (node (ref "D4") (pin "16") (pinfunction "CBUS3_16") (pintype "bidirectional"))
    )
    (net (code "133") (name "unconnected-(D4-~{CTS}-Pad6)") (class "Default")
      (node (ref "D4") (pin "6") (pinfunction "~{CTS}_6") (pintype "input"))
    )
    (net (code "134") (name "unconnected-(D4-~{RTS}-Pad2)") (class "Default")
      (node (ref "D4") (pin "2") (pinfunction "~{RTS}_2") (pintype "output"))
    )
    (net (code "135") (name "unconnected-(D8A-PA0-WKUP(PA0)-Pad23)") (class "Default")
      (node (ref "D8") (pin "23") (pinfunction "PA0-WKUP(PA0)_23") (pintype "bidirectional"))
    )
    (net (code "136") (name "unconnected-(D8A-PA8-Pad67)") (class "Default")
      (node (ref "D8") (pin "67") (pinfunction "PA8_67") (pintype "bidirectional"))
    )
    (net (code "137") (name "unconnected-(D8A-PB1-Pad36)") (class "Default")
      (node (ref "D8") (pin "36") (pinfunction "PB1_36") (pintype "bidirectional"))
    )
    (net (code "138") (name "unconnected-(D8A-PB6-Pad92)") (class "Default")
      (node (ref "D8") (pin "92") (pinfunction "PB6_92") (pintype "bidirectional"))
    )
    (net (code "139") (name "unconnected-(D8A-PB7-Pad93)") (class "Default")
      (node (ref "D8") (pin "93") (pinfunction "PB7_93") (pintype "bidirectional"))
    )
    (net (code "140") (name "unconnected-(D8A-PB14-Pad53)") (class "Default")
      (node (ref "D8") (pin "53") (pinfunction "PB14_53") (pintype "bidirectional"))
    )
    (net (code "141") (name "unconnected-(D8A-PB15-Pad54)") (class "Default")
      (node (ref "D8") (pin "54") (pinfunction "PB15_54") (pintype "bidirectional"))
    )
    (net (code "142") (name "unconnected-(D8A-PC0-Pad15)") (class "Default")
      (node (ref "D8") (pin "15") (pinfunction "PC0_15") (pintype "bidirectional"))
    )
    (net (code "143") (name "unconnected-(D8A-PC2-Pad17)") (class "Default")
      (node (ref "D8") (pin "17") (pinfunction "PC2_17") (pintype "bidirectional"))
    )
    (net (code "144") (name "unconnected-(D8A-PC3-Pad18)") (class "Default")
      (node (ref "D8") (pin "18") (pinfunction "PC3_18") (pintype "bidirectional"))
    )
    (net (code "145") (name "unconnected-(D8A-PC13-Pad7)") (class "Default")
      (node (ref "D8") (pin "7") (pinfunction "PC13_7") (pintype "bidirectional"))
    )
    (net (code "146") (name "unconnected-(D8A-PD0-Pad81)") (class "Default")
      (node (ref "D8") (pin "81") (pinfunction "PD0_81") (pintype "bidirectional"))
    )
    (net (code "147") (name "unconnected-(D8A-PD1-Pad82)") (class "Default")
      (node (ref "D8") (pin "82") (pinfunction "PD1_82") (pintype "bidirectional"))
    )
    (net (code "148") (name "unconnected-(D8A-PE1-Pad98)") (class "Default")
      (node (ref "D8") (pin "98") (pinfunction "PE1_98") (pintype "bidirectional"))
    )
    (net (code "149") (name "unconnected-(D8A-PE6-Pad5)") (class "Default")
      (node (ref "D8") (pin "5") (pinfunction "PE6_5") (pintype "bidirectional"))
    )
    (net (code "150") (name "unconnected-(D8A-PE9-Pad40)") (class "Default")
      (node (ref "D8") (pin "40") (pinfunction "PE9_40") (pintype "bidirectional"))
    )
    (net (code "151") (name "unconnected-(D8A-PE10-Pad41)") (class "Default")
      (node (ref "D8") (pin "41") (pinfunction "PE10_41") (pintype "bidirectional"))
    )
    (net (code "152") (name "unconnected-(D8A-PE11-Pad42)") (class "Default")
      (node (ref "D8") (pin "42") (pinfunction "PE11_42") (pintype "bidirectional"))
    )
    (net (code "153") (name "unconnected-(D8A-PE13-Pad44)") (class "Default")
      (node (ref "D8") (pin "44") (pinfunction "PE13_44") (pintype "bidirectional"))
    )
    (net (code "154") (name "unconnected-(D8A-PE14-Pad45)") (class "Default")
      (node (ref "D8") (pin "45") (pinfunction "PE14_45") (pintype "bidirectional"))
    )
    (net (code "155") (name "unconnected-(D8A-PE15-Pad46)") (class "Default")
      (node (ref "D8") (pin "46") (pinfunction "PE15_46") (pintype "bidirectional"))
    )
    (net (code "156") (name "unconnected-(D9-R2IN-Pad8)") (class "Default")
      (node (ref "D9") (pin "8") (pinfunction "R2IN_8") (pintype "passive"))
    )
    (net (code "157") (name "unconnected-(D9-R2OUT-Pad9)") (class "Default")
      (node (ref "D9") (pin "9") (pinfunction "R2OUT_9") (pintype "passive"))
    )
    (net (code "158") (name "unconnected-(D9-T2IN-Pad10)") (class "Default")
      (node (ref "D9") (pin "10") (pinfunction "T2IN_10") (pintype "passive"))
    )
    (net (code "159") (name "unconnected-(D9-T2OUT-Pad7)") (class "Default")
      (node (ref "D9") (pin "7") (pinfunction "T2OUT_7") (pintype "passive"))
    )
    (net (code "160") (name "unconnected-(D10-25MHZ_OUT-Pad25)") (class "Default")
      (node (ref "D10") (pin "25") (pinfunction "25MHZ_OUT_25") (pintype "output"))
    )
    (net (code "161") (name "unconnected-(D10-RXD_2{slash}PHYAD3-Pad45)") (class "Default")
      (node (ref "D10") (pin "45") (pinfunction "RXD_2/PHYAD3_45") (pintype "output"))
    )
    (net (code "162") (name "unconnected-(D10-RXD_3{slash}PHYAD4-Pad46)") (class "Default")
      (node (ref "D10") (pin "46") (pinfunction "RXD_3/PHYAD4_46") (pintype "output"))
    )
    (net (code "163") (name "unconnected-(D10-RX_CLK-Pad38)") (class "Default")
      (node (ref "D10") (pin "38") (pinfunction "RX_CLK_38") (pintype "output"))
    )
    (net (code "164") (name "unconnected-(D10-RX_ER{slash}MDIX_EN-Pad41)") (class "Default")
      (node (ref "D10") (pin "41") (pinfunction "RX_ER/MDIX_EN_41") (pintype "output"))
    )
    (net (code "165") (name "unconnected-(D10-TCK-Pad8)") (class "Default")
      (node (ref "D10") (pin "8") (pinfunction "TCK_8") (pintype "input"))
    )
    (net (code "166") (name "unconnected-(D10-TDI-Pad12)") (class "Default")
      (node (ref "D10") (pin "12") (pinfunction "TDI_12") (pintype "input"))
    )
    (net (code "167") (name "unconnected-(D10-TDO-Pad9)") (class "Default")
      (node (ref "D10") (pin "9") (pinfunction "TDO_9") (pintype "output"))
    )
    (net (code "168") (name "unconnected-(D10-TMS-Pad10)") (class "Default")
      (node (ref "D10") (pin "10") (pinfunction "TMS_10") (pintype "input"))
    )
    (net (code "169") (name "unconnected-(D10-TRST-Pad11)") (class "Default")
      (node (ref "D10") (pin "11") (pinfunction "TRST_11") (pintype "input"))
    )
    (net (code "170") (name "unconnected-(D10-TXD_2-Pad5)") (class "Default")
      (node (ref "D10") (pin "5") (pinfunction "TXD_2_5") (pintype "input"))
    )
    (net (code "171") (name "unconnected-(D10-TXD_3{slash}SNI_MODE-Pad6)") (class "Default")
      (node (ref "D10") (pin "6") (pinfunction "TXD_3/SNI_MODE_6") (pintype "input"))
    )
    (net (code "172") (name "unconnected-(D10-TX_CLK-Pad1)") (class "Default")
      (node (ref "D10") (pin "1") (pinfunction "TX_CLK_1") (pintype "output"))
    )
    (net (code "173") (name "unconnected-(D10-X2-Pad33)") (class "Default")
      (node (ref "D10") (pin "33") (pinfunction "X2_33") (pintype "output"))
    )
    (net (code "174") (name "unconnected-(VD5-A-Pad2)") (class "Default")
      (node (ref "VD5") (pin "2") (pinfunction "A_2") (pintype "passive"))
    )
    (net (code "175") (name "unconnected-(X1-ID-Pad4)") (class "Default")
      (node (ref "X1") (pin "4") (pinfunction "ID_4") (pintype "passive"))
    )
    (net (code "176") (name "unconnected-(X5-Pad4)") (class "Default")
      (node (ref "X5") (pin "4") (pinfunction "4_4") (pintype "passive"))
    )
    (net (code "177") (name "unconnected-(X5-Pad6)") (class "Default")
      (node (ref "X5") (pin "6") (pinfunction "6_6") (pintype "passive"))
    )
    (net (code "178") (name "unconnected-(X5-Pad8)") (class "Default")
      (node (ref "X5") (pin "8") (pinfunction "8_8") (pintype "passive"))
    )
    (net (code "179") (name "unconnected-(X7-Pad6)") (class "Default")
      (node (ref "X7") (pin "6") (pinfunction "6_6") (pintype "passive"))
    )
    (net (code "180") (name "unconnected-(X7-Pad7)") (class "Default")
      (node (ref "X7") (pin "7") (pinfunction "7_7") (pintype "passive"))
    )
    (net (code "181") (name "unconnected-(X7-Pad8)") (class "Default")
      (node (ref "X7") (pin "8") (pinfunction "8_8") (pintype "passive"))
    )
    (net (code "182") (name "unconnected-(X12-NC-Pad7)") (class "Default")
      (node (ref "X12") (pin "7") (pinfunction "NC_7") (pintype "passive"))
    )
  )
)
